# PixelGrid_Controller.net
KiCad netlist of a schematic drawn in EasyEDA Pro
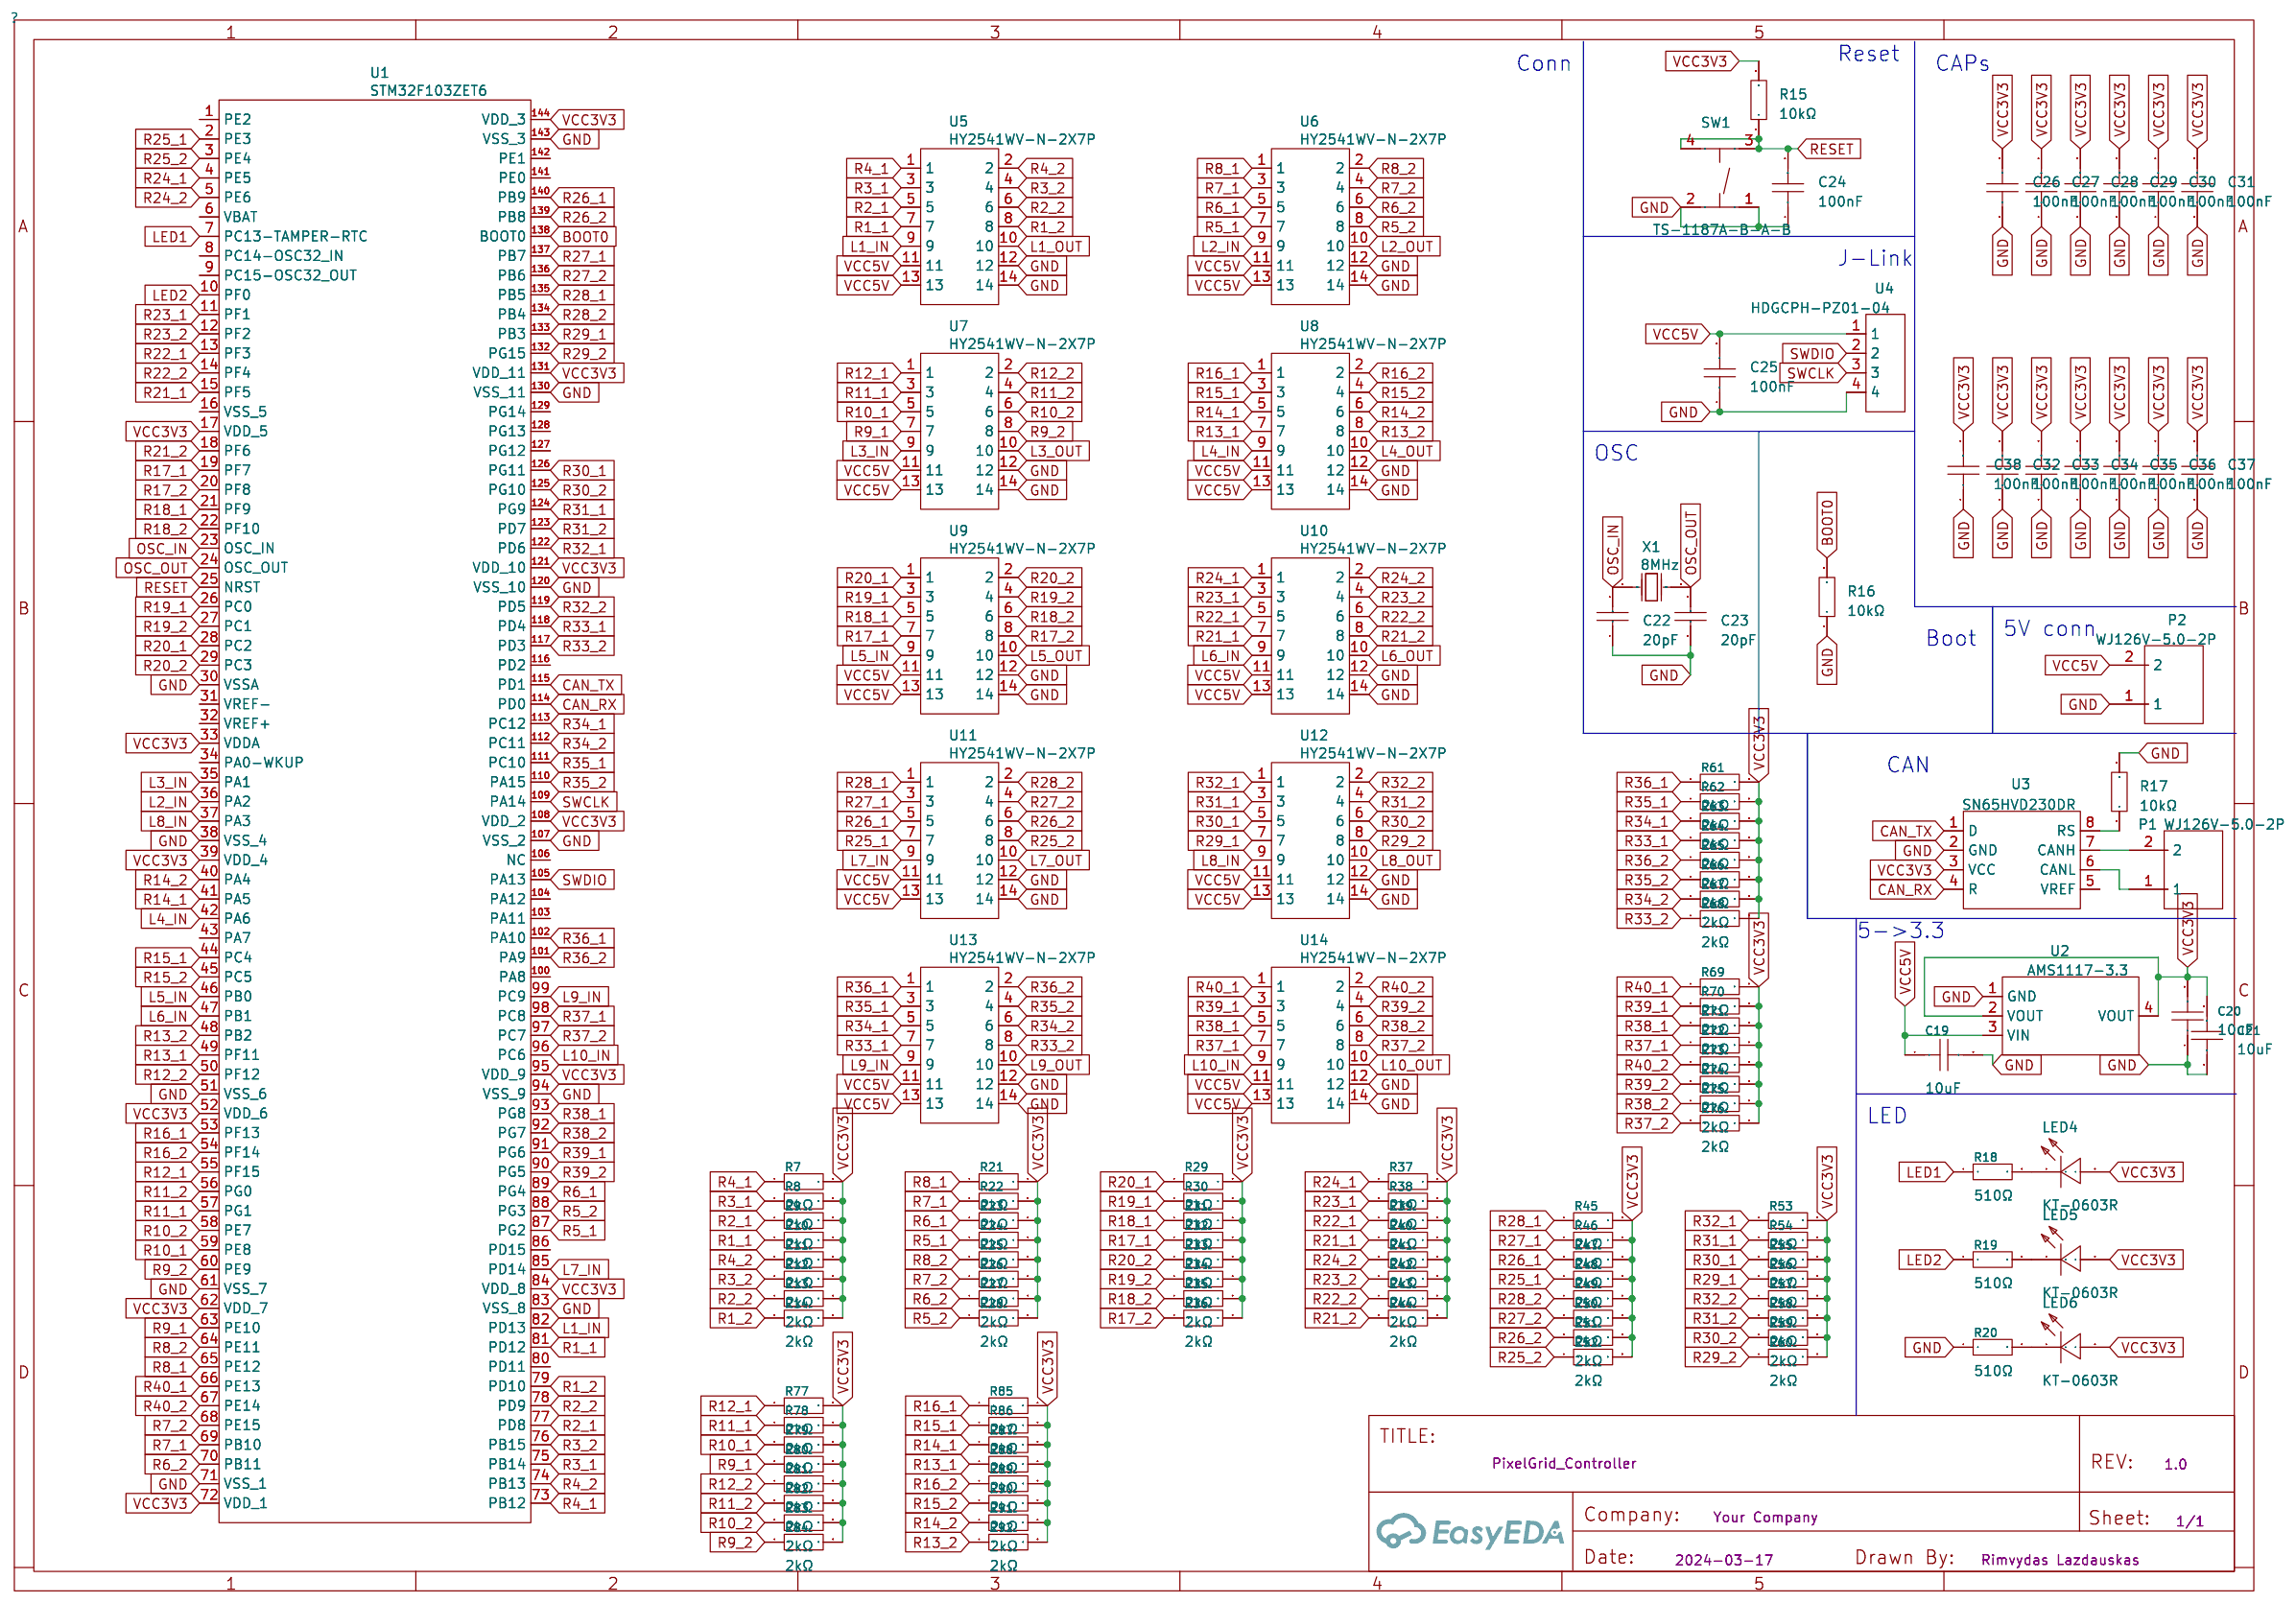
[diagram p0: schematic sheet]

(export (version "E")
  (design (tool "Eeschema 10.0.6"))
  (components
    (comp (ref "C19")
      (value "10uF")
      (footprint "easyedapro:C0603")
      (fields
        (field (name "Manufacturer Part") "CL10A106KP8NNNC")
        (field (name "Manufacturer") "SAMSUNG(三星)")
      )
      (libsource (lib "easyedapro") (part "CL10A106KP8NNNC"))
    )
    (comp (ref "C20")
      (value "10uF")
      (footprint "easyedapro:C0603")
      (fields
        (field (name "Manufacturer Part") "CL10A106KP8NNNC")
        (field (name "Manufacturer") "SAMSUNG(三星)")
      )
      (libsource (lib "easyedapro") (part "CL10A106KP8NNNC"))
    )
    (comp (ref "C21")
      (value "10uF")
      (footprint "easyedapro:C0603")
      (fields
        (field (name "Manufacturer Part") "CL10A106KP8NNNC")
        (field (name "Manufacturer") "SAMSUNG(三星)")
      )
      (libsource (lib "easyedapro") (part "CL10A106KP8NNNC"))
    )
    (comp (ref "C22")
      (value "20pF")
      (footprint "easyedapro:C0402")
      (fields (field (name "Manufacturer Part") "0402CG200J500NT") (field (name "Manufacturer") "FH(风华)"))
      (libsource (lib "easyedapro") (part "0402CG200J500NT"))
    )
    (comp (ref "C23")
      (value "20pF")
      (footprint "easyedapro:C0402")
      (fields (field (name "Manufacturer Part") "0402CG200J500NT") (field (name "Manufacturer") "FH(风华)"))
      (libsource (lib "easyedapro") (part "0402CG200J500NT"))
    )
    (comp (ref "C24")
      (value "100nF")
      (footprint "easyedapro:C0402")
      (fields
        (field (name "Manufacturer Part") "CL05B104KO5NNNC")
        (field (name "Manufacturer") "SAMSUNG(三星)")
      )
      (libsource (lib "easyedapro") (part "CL05B104KO5NNNC"))
    )
    (comp (ref "C25")
      (value "100nF")
      (footprint "easyedapro:C0402")
      (fields
        (field (name "Manufacturer Part") "CL05B104KO5NNNC")
        (field (name "Manufacturer") "SAMSUNG(三星)")
      )
      (libsource (lib "easyedapro") (part "CL05B104KO5NNNC"))
    )
    (comp (ref "C26")
      (value "100nF")
      (footprint "easyedapro:C0402")
      (fields
        (field (name "Manufacturer Part") "CL05B104KO5NNNC")
        (field (name "Manufacturer") "SAMSUNG(三星)")
      )
      (libsource (lib "easyedapro") (part "CL05B104KO5NNNC"))
    )
    (comp (ref "C27")
      (value "100nF")
      (footprint "easyedapro:C0402")
      (fields
        (field (name "Manufacturer Part") "CL05B104KO5NNNC")
        (field (name "Manufacturer") "SAMSUNG(三星)")
      )
      (libsource (lib "easyedapro") (part "CL05B104KO5NNNC"))
    )
    (comp (ref "C28")
      (value "100nF")
      (footprint "easyedapro:C0402")
      (fields
        (field (name "Manufacturer Part") "CL05B104KO5NNNC")
        (field (name "Manufacturer") "SAMSUNG(三星)")
      )
      (libsource (lib "easyedapro") (part "CL05B104KO5NNNC"))
    )
    (comp (ref "C29")
      (value "100nF")
      (footprint "easyedapro:C0402")
      (fields
        (field (name "Manufacturer Part") "CL05B104KO5NNNC")
        (field (name "Manufacturer") "SAMSUNG(三星)")
      )
      (libsource (lib "easyedapro") (part "CL05B104KO5NNNC"))
    )
    (comp (ref "C30")
      (value "100nF")
      (footprint "easyedapro:C0402")
      (fields
        (field (name "Manufacturer Part") "CL05B104KO5NNNC")
        (field (name "Manufacturer") "SAMSUNG(三星)")
      )
      (libsource (lib "easyedapro") (part "CL05B104KO5NNNC"))
    )
    (comp (ref "C31")
      (value "100nF")
      (footprint "easyedapro:C0402")
      (fields
        (field (name "Manufacturer Part") "CL05B104KO5NNNC")
        (field (name "Manufacturer") "SAMSUNG(三星)")
      )
      (libsource (lib "easyedapro") (part "CL05B104KO5NNNC"))
    )
    (comp (ref "C32")
      (value "100nF")
      (footprint "easyedapro:C0402")
      (fields
        (field (name "Manufacturer Part") "CL05B104KO5NNNC")
        (field (name "Manufacturer") "SAMSUNG(三星)")
      )
      (libsource (lib "easyedapro") (part "CL05B104KO5NNNC"))
    )
    (comp (ref "C33")
      (value "100nF")
      (footprint "easyedapro:C0402")
      (fields
        (field (name "Manufacturer Part") "CL05B104KO5NNNC")
        (field (name "Manufacturer") "SAMSUNG(三星)")
      )
      (libsource (lib "easyedapro") (part "CL05B104KO5NNNC"))
    )
    (comp (ref "C34")
      (value "100nF")
      (footprint "easyedapro:C0402")
      (fields
        (field (name "Manufacturer Part") "CL05B104KO5NNNC")
        (field (name "Manufacturer") "SAMSUNG(三星)")
      )
      (libsource (lib "easyedapro") (part "CL05B104KO5NNNC"))
    )
    (comp (ref "C35")
      (value "100nF")
      (footprint "easyedapro:C0402")
      (fields
        (field (name "Manufacturer Part") "CL05B104KO5NNNC")
        (field (name "Manufacturer") "SAMSUNG(三星)")
      )
      (libsource (lib "easyedapro") (part "CL05B104KO5NNNC"))
    )
    (comp (ref "C36")
      (value "100nF")
      (footprint "easyedapro:C0402")
      (fields
        (field (name "Manufacturer Part") "CL05B104KO5NNNC")
        (field (name "Manufacturer") "SAMSUNG(三星)")
      )
      (libsource (lib "easyedapro") (part "CL05B104KO5NNNC"))
    )
    (comp (ref "C37")
      (value "100nF")
      (footprint "easyedapro:C0402")
      (fields
        (field (name "Manufacturer Part") "CL05B104KO5NNNC")
        (field (name "Manufacturer") "SAMSUNG(三星)")
      )
      (libsource (lib "easyedapro") (part "CL05B104KO5NNNC"))
    )
    (comp (ref "C38")
      (value "100nF")
      (footprint "easyedapro:C0402")
      (fields
        (field (name "Manufacturer Part") "CL05B104KO5NNNC")
        (field (name "Manufacturer") "SAMSUNG(三星)")
      )
      (libsource (lib "easyedapro") (part "CL05B104KO5NNNC"))
    )
    (comp (ref "LED4")
      (value "KT-0603R")
      (footprint "easyedapro:LED0603-RD")
      (fields (field (name "Manufacturer") "KENTO"))
      (libsource (lib "easyedapro") (part "KT-0603R"))
    )
    (comp (ref "LED5")
      (value "KT-0603R")
      (footprint "easyedapro:LED0603-RD")
      (fields (field (name "Manufacturer") "KENTO"))
      (libsource (lib "easyedapro") (part "KT-0603R"))
    )
    (comp (ref "LED6")
      (value "KT-0603R")
      (footprint "easyedapro:LED0603-RD")
      (fields (field (name "Manufacturer") "KENTO"))
      (libsource (lib "easyedapro") (part "KT-0603R"))
    )
    (comp (ref "P1")
      (value "WJ126V-5.0-2P")
      (fields (field (name "Manufacturer") "KANGNEX(康奈克斯电气)"))
      (libsource (lib "easyedapro") (part "WJ126V-5.0-2P"))
    )
    (comp (ref "P2")
      (value "WJ126V-5.0-2P")
      (fields (field (name "Manufacturer") "KANGNEX(康奈克斯电气)"))
      (libsource (lib "easyedapro") (part "WJ126V-5.0-2P"))
    )
    (comp (ref "R7")
      (value "2kΩ")
      (footprint "easyedapro:R0402")
      (fields
        (field (name "Manufacturer Part") "0402WGF2001TCE")
        (field (name "Manufacturer") "UNI-ROYAL(厚声)")
      )
      (libsource (lib "easyedapro") (part "0402WGF2001TCE"))
    )
    (comp (ref "R8")
      (value "2kΩ")
      (footprint "easyedapro:R0402")
      (fields
        (field (name "Manufacturer Part") "0402WGF2001TCE")
        (field (name "Manufacturer") "UNI-ROYAL(厚声)")
      )
      (libsource (lib "easyedapro") (part "0402WGF2001TCE"))
    )
    (comp (ref "R9")
      (value "2kΩ")
      (footprint "easyedapro:R0402")
      (fields
        (field (name "Manufacturer Part") "0402WGF2001TCE")
        (field (name "Manufacturer") "UNI-ROYAL(厚声)")
      )
      (libsource (lib "easyedapro") (part "0402WGF2001TCE"))
    )
    (comp (ref "R10")
      (value "2kΩ")
      (footprint "easyedapro:R0402")
      (fields
        (field (name "Manufacturer Part") "0402WGF2001TCE")
        (field (name "Manufacturer") "UNI-ROYAL(厚声)")
      )
      (libsource (lib "easyedapro") (part "0402WGF2001TCE"))
    )
    (comp (ref "R11")
      (value "2kΩ")
      (footprint "easyedapro:R0402")
      (fields
        (field (name "Manufacturer Part") "0402WGF2001TCE")
        (field (name "Manufacturer") "UNI-ROYAL(厚声)")
      )
      (libsource (lib "easyedapro") (part "0402WGF2001TCE"))
    )
    (comp (ref "R12")
      (value "2kΩ")
      (footprint "easyedapro:R0402")
      (fields
        (field (name "Manufacturer Part") "0402WGF2001TCE")
        (field (name "Manufacturer") "UNI-ROYAL(厚声)")
      )
      (libsource (lib "easyedapro") (part "0402WGF2001TCE"))
    )
    (comp (ref "R13")
      (value "2kΩ")
      (footprint "easyedapro:R0402")
      (fields
        (field (name "Manufacturer Part") "0402WGF2001TCE")
        (field (name "Manufacturer") "UNI-ROYAL(厚声)")
      )
      (libsource (lib "easyedapro") (part "0402WGF2001TCE"))
    )
    (comp (ref "R14")
      (value "2kΩ")
      (footprint "easyedapro:R0402")
      (fields
        (field (name "Manufacturer Part") "0402WGF2001TCE")
        (field (name "Manufacturer") "UNI-ROYAL(厚声)")
      )
      (libsource (lib "easyedapro") (part "0402WGF2001TCE"))
    )
    (comp (ref "R15")
      (value "10kΩ")
      (footprint "easyedapro:R0402")
      (fields
        (field (name "Manufacturer Part") "0402WGF1002TCE")
        (field (name "Manufacturer") "UNI-ROYAL(厚声)")
      )
      (libsource (lib "easyedapro") (part "0402WGF1002TCE"))
    )
    (comp (ref "R16")
      (value "10kΩ")
      (footprint "easyedapro:R0402")
      (fields
        (field (name "Manufacturer Part") "0402WGF1002TCE")
        (field (name "Manufacturer") "UNI-ROYAL(厚声)")
      )
      (libsource (lib "easyedapro") (part "0402WGF1002TCE"))
    )
    (comp (ref "R17")
      (value "10kΩ")
      (footprint "easyedapro:R0402")
      (fields
        (field (name "Manufacturer Part") "0402WGF1002TCE")
        (field (name "Manufacturer") "UNI-ROYAL(厚声)")
      )
      (libsource (lib "easyedapro") (part "0402WGF1002TCE"))
    )
    (comp (ref "R18")
      (value "510Ω")
      (footprint "easyedapro:R0402")
      (fields
        (field (name "Manufacturer Part") "0402WGF5100TCE")
        (field (name "Manufacturer") "UNI-ROYAL(厚声)")
      )
      (libsource (lib "easyedapro") (part "0402WGF5100TCE"))
    )
    (comp (ref "R19")
      (value "510Ω")
      (footprint "easyedapro:R0402")
      (fields
        (field (name "Manufacturer Part") "0402WGF5100TCE")
        (field (name "Manufacturer") "UNI-ROYAL(厚声)")
      )
      (libsource (lib "easyedapro") (part "0402WGF5100TCE"))
    )
    (comp (ref "R20")
      (value "510Ω")
      (footprint "easyedapro:R0402")
      (fields
        (field (name "Manufacturer Part") "0402WGF5100TCE")
        (field (name "Manufacturer") "UNI-ROYAL(厚声)")
      )
      (libsource (lib "easyedapro") (part "0402WGF5100TCE"))
    )
    (comp (ref "R21")
      (value "2kΩ")
      (footprint "easyedapro:R0402")
      (fields
        (field (name "Manufacturer Part") "0402WGF2001TCE")
        (field (name "Manufacturer") "UNI-ROYAL(厚声)")
      )
      (libsource (lib "easyedapro") (part "0402WGF2001TCE"))
    )
    (comp (ref "R22")
      (value "2kΩ")
      (footprint "easyedapro:R0402")
      (fields
        (field (name "Manufacturer Part") "0402WGF2001TCE")
        (field (name "Manufacturer") "UNI-ROYAL(厚声)")
      )
      (libsource (lib "easyedapro") (part "0402WGF2001TCE"))
    )
    (comp (ref "R23")
      (value "2kΩ")
      (footprint "easyedapro:R0402")
      (fields
        (field (name "Manufacturer Part") "0402WGF2001TCE")
        (field (name "Manufacturer") "UNI-ROYAL(厚声)")
      )
      (libsource (lib "easyedapro") (part "0402WGF2001TCE"))
    )
    (comp (ref "R24")
      (value "2kΩ")
      (footprint "easyedapro:R0402")
      (fields
        (field (name "Manufacturer Part") "0402WGF2001TCE")
        (field (name "Manufacturer") "UNI-ROYAL(厚声)")
      )
      (libsource (lib "easyedapro") (part "0402WGF2001TCE"))
    )
    (comp (ref "R25")
      (value "2kΩ")
      (footprint "easyedapro:R0402")
      (fields
        (field (name "Manufacturer Part") "0402WGF2001TCE")
        (field (name "Manufacturer") "UNI-ROYAL(厚声)")
      )
      (libsource (lib "easyedapro") (part "0402WGF2001TCE"))
    )
    (comp (ref "R26")
      (value "2kΩ")
      (footprint "easyedapro:R0402")
      (fields
        (field (name "Manufacturer Part") "0402WGF2001TCE")
        (field (name "Manufacturer") "UNI-ROYAL(厚声)")
      )
      (libsource (lib "easyedapro") (part "0402WGF2001TCE"))
    )
    (comp (ref "R27")
      (value "2kΩ")
      (footprint "easyedapro:R0402")
      (fields
        (field (name "Manufacturer Part") "0402WGF2001TCE")
        (field (name "Manufacturer") "UNI-ROYAL(厚声)")
      )
      (libsource (lib "easyedapro") (part "0402WGF2001TCE"))
    )
    (comp (ref "R28")
      (value "2kΩ")
      (footprint "easyedapro:R0402")
      (fields
        (field (name "Manufacturer Part") "0402WGF2001TCE")
        (field (name "Manufacturer") "UNI-ROYAL(厚声)")
      )
      (libsource (lib "easyedapro") (part "0402WGF2001TCE"))
    )
    (comp (ref "R29")
      (value "2kΩ")
      (footprint "easyedapro:R0402")
      (fields
        (field (name "Manufacturer Part") "0402WGF2001TCE")
        (field (name "Manufacturer") "UNI-ROYAL(厚声)")
      )
      (libsource (lib "easyedapro") (part "0402WGF2001TCE"))
    )
    (comp (ref "R30")
      (value "2kΩ")
      (footprint "easyedapro:R0402")
      (fields
        (field (name "Manufacturer Part") "0402WGF2001TCE")
        (field (name "Manufacturer") "UNI-ROYAL(厚声)")
      )
      (libsource (lib "easyedapro") (part "0402WGF2001TCE"))
    )
    (comp (ref "R31")
      (value "2kΩ")
      (footprint "easyedapro:R0402")
      (fields
        (field (name "Manufacturer Part") "0402WGF2001TCE")
        (field (name "Manufacturer") "UNI-ROYAL(厚声)")
      )
      (libsource (lib "easyedapro") (part "0402WGF2001TCE"))
    )
    (comp (ref "R32")
      (value "2kΩ")
      (footprint "easyedapro:R0402")
      (fields
        (field (name "Manufacturer Part") "0402WGF2001TCE")
        (field (name "Manufacturer") "UNI-ROYAL(厚声)")
      )
      (libsource (lib "easyedapro") (part "0402WGF2001TCE"))
    )
    (comp (ref "R33")
      (value "2kΩ")
      (footprint "easyedapro:R0402")
      (fields
        (field (name "Manufacturer Part") "0402WGF2001TCE")
        (field (name "Manufacturer") "UNI-ROYAL(厚声)")
      )
      (libsource (lib "easyedapro") (part "0402WGF2001TCE"))
    )
    (comp (ref "R34")
      (value "2kΩ")
      (footprint "easyedapro:R0402")
      (fields
        (field (name "Manufacturer Part") "0402WGF2001TCE")
        (field (name "Manufacturer") "UNI-ROYAL(厚声)")
      )
      (libsource (lib "easyedapro") (part "0402WGF2001TCE"))
    )
    (comp (ref "R35")
      (value "2kΩ")
      (footprint "easyedapro:R0402")
      (fields
        (field (name "Manufacturer Part") "0402WGF2001TCE")
        (field (name "Manufacturer") "UNI-ROYAL(厚声)")
      )
      (libsource (lib "easyedapro") (part "0402WGF2001TCE"))
    )
    (comp (ref "R36")
      (value "2kΩ")
      (footprint "easyedapro:R0402")
      (fields
        (field (name "Manufacturer Part") "0402WGF2001TCE")
        (field (name "Manufacturer") "UNI-ROYAL(厚声)")
      )
      (libsource (lib "easyedapro") (part "0402WGF2001TCE"))
    )
    (comp (ref "R37")
      (value "2kΩ")
      (footprint "easyedapro:R0402")
      (fields
        (field (name "Manufacturer Part") "0402WGF2001TCE")
        (field (name "Manufacturer") "UNI-ROYAL(厚声)")
      )
      (libsource (lib "easyedapro") (part "0402WGF2001TCE"))
    )
    (comp (ref "R38")
      (value "2kΩ")
      (footprint "easyedapro:R0402")
      (fields
        (field (name "Manufacturer Part") "0402WGF2001TCE")
        (field (name "Manufacturer") "UNI-ROYAL(厚声)")
      )
      (libsource (lib "easyedapro") (part "0402WGF2001TCE"))
    )
    (comp (ref "R39")
      (value "2kΩ")
      (footprint "easyedapro:R0402")
      (fields
        (field (name "Manufacturer Part") "0402WGF2001TCE")
        (field (name "Manufacturer") "UNI-ROYAL(厚声)")
      )
      (libsource (lib "easyedapro") (part "0402WGF2001TCE"))
    )
    (comp (ref "R40")
      (value "2kΩ")
      (footprint "easyedapro:R0402")
      (fields
        (field (name "Manufacturer Part") "0402WGF2001TCE")
        (field (name "Manufacturer") "UNI-ROYAL(厚声)")
      )
      (libsource (lib "easyedapro") (part "0402WGF2001TCE"))
    )
    (comp (ref "R41")
      (value "2kΩ")
      (footprint "easyedapro:R0402")
      (fields
        (field (name "Manufacturer Part") "0402WGF2001TCE")
        (field (name "Manufacturer") "UNI-ROYAL(厚声)")
      )
      (libsource (lib "easyedapro") (part "0402WGF2001TCE"))
    )
    (comp (ref "R42")
      (value "2kΩ")
      (footprint "easyedapro:R0402")
      (fields
        (field (name "Manufacturer Part") "0402WGF2001TCE")
        (field (name "Manufacturer") "UNI-ROYAL(厚声)")
      )
      (libsource (lib "easyedapro") (part "0402WGF2001TCE"))
    )
    (comp (ref "R43")
      (value "2kΩ")
      (footprint "easyedapro:R0402")
      (fields
        (field (name "Manufacturer Part") "0402WGF2001TCE")
        (field (name "Manufacturer") "UNI-ROYAL(厚声)")
      )
      (libsource (lib "easyedapro") (part "0402WGF2001TCE"))
    )
    (comp (ref "R44")
      (value "2kΩ")
      (footprint "easyedapro:R0402")
      (fields
        (field (name "Manufacturer Part") "0402WGF2001TCE")
        (field (name "Manufacturer") "UNI-ROYAL(厚声)")
      )
      (libsource (lib "easyedapro") (part "0402WGF2001TCE"))
    )
    (comp (ref "R45")
      (value "2kΩ")
      (footprint "easyedapro:R0402")
      (fields
        (field (name "Manufacturer Part") "0402WGF2001TCE")
        (field (name "Manufacturer") "UNI-ROYAL(厚声)")
      )
      (libsource (lib "easyedapro") (part "0402WGF2001TCE"))
    )
    (comp (ref "R46")
      (value "2kΩ")
      (footprint "easyedapro:R0402")
      (fields
        (field (name "Manufacturer Part") "0402WGF2001TCE")
        (field (name "Manufacturer") "UNI-ROYAL(厚声)")
      )
      (libsource (lib "easyedapro") (part "0402WGF2001TCE"))
    )
    (comp (ref "R47")
      (value "2kΩ")
      (footprint "easyedapro:R0402")
      (fields
        (field (name "Manufacturer Part") "0402WGF2001TCE")
        (field (name "Manufacturer") "UNI-ROYAL(厚声)")
      )
      (libsource (lib "easyedapro") (part "0402WGF2001TCE"))
    )
    (comp (ref "R48")
      (value "2kΩ")
      (footprint "easyedapro:R0402")
      (fields
        (field (name "Manufacturer Part") "0402WGF2001TCE")
        (field (name "Manufacturer") "UNI-ROYAL(厚声)")
      )
      (libsource (lib "easyedapro") (part "0402WGF2001TCE"))
    )
    (comp (ref "R49")
      (value "2kΩ")
      (footprint "easyedapro:R0402")
      (fields
        (field (name "Manufacturer Part") "0402WGF2001TCE")
        (field (name "Manufacturer") "UNI-ROYAL(厚声)")
      )
      (libsource (lib "easyedapro") (part "0402WGF2001TCE"))
    )
    (comp (ref "R50")
      (value "2kΩ")
      (footprint "easyedapro:R0402")
      (fields
        (field (name "Manufacturer Part") "0402WGF2001TCE")
        (field (name "Manufacturer") "UNI-ROYAL(厚声)")
      )
      (libsource (lib "easyedapro") (part "0402WGF2001TCE"))
    )
    (comp (ref "R51")
      (value "2kΩ")
      (footprint "easyedapro:R0402")
      (fields
        (field (name "Manufacturer Part") "0402WGF2001TCE")
        (field (name "Manufacturer") "UNI-ROYAL(厚声)")
      )
      (libsource (lib "easyedapro") (part "0402WGF2001TCE"))
    )
    (comp (ref "R52")
      (value "2kΩ")
      (footprint "easyedapro:R0402")
      (fields
        (field (name "Manufacturer Part") "0402WGF2001TCE")
        (field (name "Manufacturer") "UNI-ROYAL(厚声)")
      )
      (libsource (lib "easyedapro") (part "0402WGF2001TCE"))
    )
    (comp (ref "R53")
      (value "2kΩ")
      (footprint "easyedapro:R0402")
      (fields
        (field (name "Manufacturer Part") "0402WGF2001TCE")
        (field (name "Manufacturer") "UNI-ROYAL(厚声)")
      )
      (libsource (lib "easyedapro") (part "0402WGF2001TCE"))
    )
    (comp (ref "R54")
      (value "2kΩ")
      (footprint "easyedapro:R0402")
      (fields
        (field (name "Manufacturer Part") "0402WGF2001TCE")
        (field (name "Manufacturer") "UNI-ROYAL(厚声)")
      )
      (libsource (lib "easyedapro") (part "0402WGF2001TCE"))
    )
    (comp (ref "R55")
      (value "2kΩ")
      (footprint "easyedapro:R0402")
      (fields
        (field (name "Manufacturer Part") "0402WGF2001TCE")
        (field (name "Manufacturer") "UNI-ROYAL(厚声)")
      )
      (libsource (lib "easyedapro") (part "0402WGF2001TCE"))
    )
    (comp (ref "R56")
      (value "2kΩ")
      (footprint "easyedapro:R0402")
      (fields
        (field (name "Manufacturer Part") "0402WGF2001TCE")
        (field (name "Manufacturer") "UNI-ROYAL(厚声)")
      )
      (libsource (lib "easyedapro") (part "0402WGF2001TCE"))
    )
    (comp (ref "R57")
      (value "2kΩ")
      (footprint "easyedapro:R0402")
      (fields
        (field (name "Manufacturer Part") "0402WGF2001TCE")
        (field (name "Manufacturer") "UNI-ROYAL(厚声)")
      )
      (libsource (lib "easyedapro") (part "0402WGF2001TCE"))
    )
    (comp (ref "R58")
      (value "2kΩ")
      (footprint "easyedapro:R0402")
      (fields
        (field (name "Manufacturer Part") "0402WGF2001TCE")
        (field (name "Manufacturer") "UNI-ROYAL(厚声)")
      )
      (libsource (lib "easyedapro") (part "0402WGF2001TCE"))
    )
    (comp (ref "R59")
      (value "2kΩ")
      (footprint "easyedapro:R0402")
      (fields
        (field (name "Manufacturer Part") "0402WGF2001TCE")
        (field (name "Manufacturer") "UNI-ROYAL(厚声)")
      )
      (libsource (lib "easyedapro") (part "0402WGF2001TCE"))
    )
    (comp (ref "R60")
      (value "2kΩ")
      (footprint "easyedapro:R0402")
      (fields
        (field (name "Manufacturer Part") "0402WGF2001TCE")
        (field (name "Manufacturer") "UNI-ROYAL(厚声)")
      )
      (libsource (lib "easyedapro") (part "0402WGF2001TCE"))
    )
    (comp (ref "R61")
      (value "2kΩ")
      (footprint "easyedapro:R0402")
      (fields
        (field (name "Manufacturer Part") "0402WGF2001TCE")
        (field (name "Manufacturer") "UNI-ROYAL(厚声)")
      )
      (libsource (lib "easyedapro") (part "0402WGF2001TCE"))
    )
    (comp (ref "R62")
      (value "2kΩ")
      (footprint "easyedapro:R0402")
      (fields
        (field (name "Manufacturer Part") "0402WGF2001TCE")
        (field (name "Manufacturer") "UNI-ROYAL(厚声)")
      )
      (libsource (lib "easyedapro") (part "0402WGF2001TCE"))
    )
    (comp (ref "R63")
      (value "2kΩ")
      (footprint "easyedapro:R0402")
      (fields
        (field (name "Manufacturer Part") "0402WGF2001TCE")
        (field (name "Manufacturer") "UNI-ROYAL(厚声)")
      )
      (libsource (lib "easyedapro") (part "0402WGF2001TCE"))
    )
    (comp (ref "R64")
      (value "2kΩ")
      (footprint "easyedapro:R0402")
      (fields
        (field (name "Manufacturer Part") "0402WGF2001TCE")
        (field (name "Manufacturer") "UNI-ROYAL(厚声)")
      )
      (libsource (lib "easyedapro") (part "0402WGF2001TCE"))
    )
    (comp (ref "R65")
      (value "2kΩ")
      (footprint "easyedapro:R0402")
      (fields
        (field (name "Manufacturer Part") "0402WGF2001TCE")
        (field (name "Manufacturer") "UNI-ROYAL(厚声)")
      )
      (libsource (lib "easyedapro") (part "0402WGF2001TCE"))
    )
    (comp (ref "R66")
      (value "2kΩ")
      (footprint "easyedapro:R0402")
      (fields
        (field (name "Manufacturer Part") "0402WGF2001TCE")
        (field (name "Manufacturer") "UNI-ROYAL(厚声)")
      )
      (libsource (lib "easyedapro") (part "0402WGF2001TCE"))
    )
    (comp (ref "R67")
      (value "2kΩ")
      (footprint "easyedapro:R0402")
      (fields
        (field (name "Manufacturer Part") "0402WGF2001TCE")
        (field (name "Manufacturer") "UNI-ROYAL(厚声)")
      )
      (libsource (lib "easyedapro") (part "0402WGF2001TCE"))
    )
    (comp (ref "R68")
      (value "2kΩ")
      (footprint "easyedapro:R0402")
      (fields
        (field (name "Manufacturer Part") "0402WGF2001TCE")
        (field (name "Manufacturer") "UNI-ROYAL(厚声)")
      )
      (libsource (lib "easyedapro") (part "0402WGF2001TCE"))
    )
    (comp (ref "R69")
      (value "2kΩ")
      (footprint "easyedapro:R0402")
      (fields
        (field (name "Manufacturer Part") "0402WGF2001TCE")
        (field (name "Manufacturer") "UNI-ROYAL(厚声)")
      )
      (libsource (lib "easyedapro") (part "0402WGF2001TCE"))
    )
    (comp (ref "R70")
      (value "2kΩ")
      (footprint "easyedapro:R0402")
      (fields
        (field (name "Manufacturer Part") "0402WGF2001TCE")
        (field (name "Manufacturer") "UNI-ROYAL(厚声)")
      )
      (libsource (lib "easyedapro") (part "0402WGF2001TCE"))
    )
    (comp (ref "R71")
      (value "2kΩ")
      (footprint "easyedapro:R0402")
      (fields
        (field (name "Manufacturer Part") "0402WGF2001TCE")
        (field (name "Manufacturer") "UNI-ROYAL(厚声)")
      )
      (libsource (lib "easyedapro") (part "0402WGF2001TCE"))
    )
    (comp (ref "R72")
      (value "2kΩ")
      (footprint "easyedapro:R0402")
      (fields
        (field (name "Manufacturer Part") "0402WGF2001TCE")
        (field (name "Manufacturer") "UNI-ROYAL(厚声)")
      )
      (libsource (lib "easyedapro") (part "0402WGF2001TCE"))
    )
    (comp (ref "R73")
      (value "2kΩ")
      (footprint "easyedapro:R0402")
      (fields
        (field (name "Manufacturer Part") "0402WGF2001TCE")
        (field (name "Manufacturer") "UNI-ROYAL(厚声)")
      )
      (libsource (lib "easyedapro") (part "0402WGF2001TCE"))
    )
    (comp (ref "R74")
      (value "2kΩ")
      (footprint "easyedapro:R0402")
      (fields
        (field (name "Manufacturer Part") "0402WGF2001TCE")
        (field (name "Manufacturer") "UNI-ROYAL(厚声)")
      )
      (libsource (lib "easyedapro") (part "0402WGF2001TCE"))
    )
    (comp (ref "R75")
      (value "2kΩ")
      (footprint "easyedapro:R0402")
      (fields
        (field (name "Manufacturer Part") "0402WGF2001TCE")
        (field (name "Manufacturer") "UNI-ROYAL(厚声)")
      )
      (libsource (lib "easyedapro") (part "0402WGF2001TCE"))
    )
    (comp (ref "R76")
      (value "2kΩ")
      (footprint "easyedapro:R0402")
      (fields
        (field (name "Manufacturer Part") "0402WGF2001TCE")
        (field (name "Manufacturer") "UNI-ROYAL(厚声)")
      )
      (libsource (lib "easyedapro") (part "0402WGF2001TCE"))
    )
    (comp (ref "R77")
      (value "2kΩ")
      (footprint "easyedapro:R0402")
      (fields
        (field (name "Manufacturer Part") "0402WGF2001TCE")
        (field (name "Manufacturer") "UNI-ROYAL(厚声)")
      )
      (libsource (lib "easyedapro") (part "0402WGF2001TCE"))
    )
    (comp (ref "R78")
      (value "2kΩ")
      (footprint "easyedapro:R0402")
      (fields
        (field (name "Manufacturer Part") "0402WGF2001TCE")
        (field (name "Manufacturer") "UNI-ROYAL(厚声)")
      )
      (libsource (lib "easyedapro") (part "0402WGF2001TCE"))
    )
    (comp (ref "R79")
      (value "2kΩ")
      (footprint "easyedapro:R0402")
      (fields
        (field (name "Manufacturer Part") "0402WGF2001TCE")
        (field (name "Manufacturer") "UNI-ROYAL(厚声)")
      )
      (libsource (lib "easyedapro") (part "0402WGF2001TCE"))
    )
    (comp (ref "R80")
      (value "2kΩ")
      (footprint "easyedapro:R0402")
      (fields
        (field (name "Manufacturer Part") "0402WGF2001TCE")
        (field (name "Manufacturer") "UNI-ROYAL(厚声)")
      )
      (libsource (lib "easyedapro") (part "0402WGF2001TCE"))
    )
    (comp (ref "R81")
      (value "2kΩ")
      (footprint "easyedapro:R0402")
      (fields
        (field (name "Manufacturer Part") "0402WGF2001TCE")
        (field (name "Manufacturer") "UNI-ROYAL(厚声)")
      )
      (libsource (lib "easyedapro") (part "0402WGF2001TCE"))
    )
    (comp (ref "R82")
      (value "2kΩ")
      (footprint "easyedapro:R0402")
      (fields
        (field (name "Manufacturer Part") "0402WGF2001TCE")
        (field (name "Manufacturer") "UNI-ROYAL(厚声)")
      )
      (libsource (lib "easyedapro") (part "0402WGF2001TCE"))
    )
    (comp (ref "R83")
      (value "2kΩ")
      (footprint "easyedapro:R0402")
      (fields
        (field (name "Manufacturer Part") "0402WGF2001TCE")
        (field (name "Manufacturer") "UNI-ROYAL(厚声)")
      )
      (libsource (lib "easyedapro") (part "0402WGF2001TCE"))
    )
    (comp (ref "R84")
      (value "2kΩ")
      (footprint "easyedapro:R0402")
      (fields
        (field (name "Manufacturer Part") "0402WGF2001TCE")
        (field (name "Manufacturer") "UNI-ROYAL(厚声)")
      )
      (libsource (lib "easyedapro") (part "0402WGF2001TCE"))
    )
    (comp (ref "R85")
      (value "2kΩ")
      (footprint "easyedapro:R0402")
      (fields
        (field (name "Manufacturer Part") "0402WGF2001TCE")
        (field (name "Manufacturer") "UNI-ROYAL(厚声)")
      )
      (libsource (lib "easyedapro") (part "0402WGF2001TCE"))
    )
    (comp (ref "R86")
      (value "2kΩ")
      (footprint "easyedapro:R0402")
      (fields
        (field (name "Manufacturer Part") "0402WGF2001TCE")
        (field (name "Manufacturer") "UNI-ROYAL(厚声)")
      )
      (libsource (lib "easyedapro") (part "0402WGF2001TCE"))
    )
    (comp (ref "R87")
      (value "2kΩ")
      (footprint "easyedapro:R0402")
      (fields
        (field (name "Manufacturer Part") "0402WGF2001TCE")
        (field (name "Manufacturer") "UNI-ROYAL(厚声)")
      )
      (libsource (lib "easyedapro") (part "0402WGF2001TCE"))
    )
    (comp (ref "R88")
      (value "2kΩ")
      (footprint "easyedapro:R0402")
      (fields
        (field (name "Manufacturer Part") "0402WGF2001TCE")
        (field (name "Manufacturer") "UNI-ROYAL(厚声)")
      )
      (libsource (lib "easyedapro") (part "0402WGF2001TCE"))
    )
    (comp (ref "R89")
      (value "2kΩ")
      (footprint "easyedapro:R0402")
      (fields
        (field (name "Manufacturer Part") "0402WGF2001TCE")
        (field (name "Manufacturer") "UNI-ROYAL(厚声)")
      )
      (libsource (lib "easyedapro") (part "0402WGF2001TCE"))
    )
    (comp (ref "R90")
      (value "2kΩ")
      (footprint "easyedapro:R0402")
      (fields
        (field (name "Manufacturer Part") "0402WGF2001TCE")
        (field (name "Manufacturer") "UNI-ROYAL(厚声)")
      )
      (libsource (lib "easyedapro") (part "0402WGF2001TCE"))
    )
    (comp (ref "R91")
      (value "2kΩ")
      (footprint "easyedapro:R0402")
      (fields
        (field (name "Manufacturer Part") "0402WGF2001TCE")
        (field (name "Manufacturer") "UNI-ROYAL(厚声)")
      )
      (libsource (lib "easyedapro") (part "0402WGF2001TCE"))
    )
    (comp (ref "R92")
      (value "2kΩ")
      (footprint "easyedapro:R0402")
      (fields
        (field (name "Manufacturer Part") "0402WGF2001TCE")
        (field (name "Manufacturer") "UNI-ROYAL(厚声)")
      )
      (libsource (lib "easyedapro") (part "0402WGF2001TCE"))
    )
    (comp (ref "SW1")
      (value "TS-1187A-B-A-B")
      (fields (field (name "Manufacturer") "XKB Connectivity(中国星坤)"))
      (libsource (lib "easyedapro") (part "TS-1187A-B-A-B"))
    )
    (comp (ref "U1")
      (value "STM32F103ZET6")
      (fields (field (name "Manufacturer") "ST(意法半导体)"))
      (libsource (lib "easyedapro") (part "STM32F103ZET6"))
    )
    (comp (ref "U2")
      (value "AMS1117-3.3")
      (fields (field (name "Manufacturer") "AMS"))
      (libsource (lib "easyedapro") (part "AMS1117-3.3"))
    )
    (comp (ref "U3")
      (value "SN65HVD230DR")
      (fields (field (name "Manufacturer") "TI(德州仪器)"))
      (libsource (lib "easyedapro") (part "SN65HVD230DR"))
    )
    (comp (ref "U4")
      (value "HDGCPH-PZ01-04")
      (fields (field (name "Manufacturer") "HDGC(华德共创)"))
      (libsource (lib "easyedapro") (part "HDGCPH-PZ01-04"))
    )
    (comp (ref "U5")
      (value "HY2541WV-N-2X7P")
      (fields
        (field (name "Manufacturer Part") "HY2541WV-N-2x7P")
        (field (name "Manufacturer") "HanElectricity(瀚源)")
      )
      (libsource (lib "easyedapro") (part "HY2541WV-N-2X7P"))
    )
    (comp (ref "U6")
      (value "HY2541WV-N-2X7P")
      (fields
        (field (name "Manufacturer Part") "HY2541WV-N-2x7P")
        (field (name "Manufacturer") "HanElectricity(瀚源)")
      )
      (libsource (lib "easyedapro") (part "HY2541WV-N-2X7P"))
    )
    (comp (ref "U7")
      (value "HY2541WV-N-2X7P")
      (fields
        (field (name "Manufacturer Part") "HY2541WV-N-2x7P")
        (field (name "Manufacturer") "HanElectricity(瀚源)")
      )
      (libsource (lib "easyedapro") (part "HY2541WV-N-2X7P"))
    )
    (comp (ref "U8")
      (value "HY2541WV-N-2X7P")
      (fields
        (field (name "Manufacturer Part") "HY2541WV-N-2x7P")
        (field (name "Manufacturer") "HanElectricity(瀚源)")
      )
      (libsource (lib "easyedapro") (part "HY2541WV-N-2X7P"))
    )
    (comp (ref "U9")
      (value "HY2541WV-N-2X7P")
      (fields
        (field (name "Manufacturer Part") "HY2541WV-N-2x7P")
        (field (name "Manufacturer") "HanElectricity(瀚源)")
      )
      (libsource (lib "easyedapro") (part "HY2541WV-N-2X7P"))
    )
    (comp (ref "U10")
      (value "HY2541WV-N-2X7P")
      (fields
        (field (name "Manufacturer Part") "HY2541WV-N-2x7P")
        (field (name "Manufacturer") "HanElectricity(瀚源)")
      )
      (libsource (lib "easyedapro") (part "HY2541WV-N-2X7P"))
    )
    (comp (ref "U11")
      (value "HY2541WV-N-2X7P")
      (fields
        (field (name "Manufacturer Part") "HY2541WV-N-2x7P")
        (field (name "Manufacturer") "HanElectricity(瀚源)")
      )
      (libsource (lib "easyedapro") (part "HY2541WV-N-2X7P"))
    )
    (comp (ref "U12")
      (value "HY2541WV-N-2X7P")
      (fields
        (field (name "Manufacturer Part") "HY2541WV-N-2x7P")
        (field (name "Manufacturer") "HanElectricity(瀚源)")
      )
      (libsource (lib "easyedapro") (part "HY2541WV-N-2X7P"))
    )
    (comp (ref "U13")
      (value "HY2541WV-N-2X7P")
      (fields
        (field (name "Manufacturer Part") "HY2541WV-N-2x7P")
        (field (name "Manufacturer") "HanElectricity(瀚源)")
      )
      (libsource (lib "easyedapro") (part "HY2541WV-N-2X7P"))
    )
    (comp (ref "U14")
      (value "HY2541WV-N-2X7P")
      (fields
        (field (name "Manufacturer Part") "HY2541WV-N-2x7P")
        (field (name "Manufacturer") "HanElectricity(瀚源)")
      )
      (libsource (lib "easyedapro") (part "HY2541WV-N-2X7P"))
    )
    (comp (ref "X1")
      (value "8MHz")
      (fields (field (name "Manufacturer Part") "X50328MSB2GI") (field (name "Manufacturer") "YXC(扬兴晶振)"))
      (libsource (lib "easyedapro") (part "8MHz"))
    )
  )
  (nets
    (net (code "1") (name "BOOT0") (class "Default")
      (node (ref "R16") (pin "2") (pinfunction "2_2") (pintype "input"))
      (node (ref "U1") (pin "138") (pinfunction "BOOT0_138") (pintype "unspecified"))
    )
    (net (code "2") (name "CAN_RX") (class "Default")
      (node (ref "U1") (pin "114") (pinfunction "PD0_114") (pintype "unspecified"))
      (node (ref "U3") (pin "4") (pinfunction "R_4") (pintype "unspecified"))
    )
    (net (code "3") (name "CAN_TX") (class "Default")
      (node (ref "U1") (pin "115") (pinfunction "PD1_115") (pintype "unspecified"))
      (node (ref "U3") (pin "1") (pinfunction "D_1") (pintype "unspecified"))
    )
    (net (code "4") (name "GND") (class "Default")
      (node (ref "C19") (pin "2") (pinfunction "2_2") (pintype "input"))
      (node (ref "C20") (pin "1") (pinfunction "1_1") (pintype "input"))
      (node (ref "C21") (pin "1") (pinfunction "1_1") (pintype "input"))
      (node (ref "C22") (pin "1") (pinfunction "1_1") (pintype "input"))
      (node (ref "C23") (pin "1") (pinfunction "1_1") (pintype "input"))
      (node (ref "C24") (pin "1") (pinfunction "1_1") (pintype "unspecified"))
      (node (ref "C25") (pin "1") (pinfunction "1_1") (pintype "unspecified"))
      (node (ref "C26") (pin "1") (pinfunction "1_1") (pintype "unspecified"))
      (node (ref "C27") (pin "1") (pinfunction "1_1") (pintype "unspecified"))
      (node (ref "C28") (pin "1") (pinfunction "1_1") (pintype "unspecified"))
      (node (ref "C29") (pin "1") (pinfunction "1_1") (pintype "unspecified"))
      (node (ref "C30") (pin "1") (pinfunction "1_1") (pintype "unspecified"))
      (node (ref "C31") (pin "1") (pinfunction "1_1") (pintype "unspecified"))
      (node (ref "C32") (pin "1") (pinfunction "1_1") (pintype "unspecified"))
      (node (ref "C33") (pin "1") (pinfunction "1_1") (pintype "unspecified"))
      (node (ref "C34") (pin "1") (pinfunction "1_1") (pintype "unspecified"))
      (node (ref "C35") (pin "1") (pinfunction "1_1") (pintype "unspecified"))
      (node (ref "C36") (pin "1") (pinfunction "1_1") (pintype "unspecified"))
      (node (ref "C37") (pin "1") (pinfunction "1_1") (pintype "unspecified"))
      (node (ref "C38") (pin "1") (pinfunction "1_1") (pintype "unspecified"))
      (node (ref "P2") (pin "1") (pinfunction "1_1") (pintype "input"))
      (node (ref "R16") (pin "1") (pinfunction "1_1") (pintype "input"))
      (node (ref "R17") (pin "2") (pinfunction "2_2") (pintype "input"))
      (node (ref "R20") (pin "1") (pinfunction "1_1") (pintype "input"))
      (node (ref "SW1") (pin "1") (pinfunction "A_1") (pintype "unspecified"))
      (node (ref "SW1") (pin "2") (pinfunction "B_2") (pintype "unspecified"))
      (node (ref "U1") (pin "107") (pinfunction "VSS_2_107") (pintype "unspecified"))
      (node (ref "U1") (pin "120") (pinfunction "VSS_10_120") (pintype "unspecified"))
      (node (ref "U1") (pin "130") (pinfunction "VSS_11_130") (pintype "unspecified"))
      (node (ref "U1") (pin "143") (pinfunction "VSS_3_143") (pintype "unspecified"))
      (node (ref "U1") (pin "30") (pinfunction "VSSA_30") (pintype "unspecified"))
      (node (ref "U1") (pin "38") (pinfunction "VSS_4_38") (pintype "unspecified"))
      (node (ref "U1") (pin "51") (pinfunction "VSS_6_51") (pintype "unspecified"))
      (node (ref "U1") (pin "61") (pinfunction "VSS_7_61") (pintype "unspecified"))
      (node (ref "U1") (pin "71") (pinfunction "VSS_1_71") (pintype "unspecified"))
      (node (ref "U1") (pin "83") (pinfunction "VSS_8_83") (pintype "unspecified"))
      (node (ref "U1") (pin "94") (pinfunction "VSS_9_94") (pintype "unspecified"))
      (node (ref "U10") (pin "12") (pinfunction "12_12") (pintype "unspecified"))
      (node (ref "U10") (pin "14") (pinfunction "14_14") (pintype "unspecified"))
      (node (ref "U11") (pin "12") (pinfunction "12_12") (pintype "unspecified"))
      (node (ref "U11") (pin "14") (pinfunction "14_14") (pintype "unspecified"))
      (node (ref "U12") (pin "12") (pinfunction "12_12") (pintype "unspecified"))
      (node (ref "U12") (pin "14") (pinfunction "14_14") (pintype "unspecified"))
      (node (ref "U13") (pin "12") (pinfunction "12_12") (pintype "unspecified"))
      (node (ref "U13") (pin "14") (pinfunction "14_14") (pintype "unspecified"))
      (node (ref "U14") (pin "12") (pinfunction "12_12") (pintype "unspecified"))
      (node (ref "U14") (pin "14") (pinfunction "14_14") (pintype "unspecified"))
      (node (ref "U2") (pin "1") (pinfunction "GND_1") (pintype "unspecified"))
      (node (ref "U3") (pin "2") (pinfunction "GND_2") (pintype "unspecified"))
      (node (ref "U4") (pin "4") (pinfunction "4_4") (pintype "unspecified"))
      (node (ref "U5") (pin "12") (pinfunction "12_12") (pintype "unspecified"))
      (node (ref "U5") (pin "14") (pinfunction "14_14") (pintype "unspecified"))
      (node (ref "U6") (pin "12") (pinfunction "12_12") (pintype "unspecified"))
      (node (ref "U6") (pin "14") (pinfunction "14_14") (pintype "unspecified"))
      (node (ref "U7") (pin "12") (pinfunction "12_12") (pintype "unspecified"))
      (node (ref "U7") (pin "14") (pinfunction "14_14") (pintype "unspecified"))
      (node (ref "U8") (pin "12") (pinfunction "12_12") (pintype "unspecified"))
      (node (ref "U8") (pin "14") (pinfunction "14_14") (pintype "unspecified"))
      (node (ref "U9") (pin "12") (pinfunction "12_12") (pintype "unspecified"))
      (node (ref "U9") (pin "14") (pinfunction "14_14") (pintype "unspecified"))
    )
    (net (code "5") (name "L1_IN") (class "Default")
      (node (ref "U1") (pin "82") (pinfunction "PD13_82") (pintype "unspecified"))
      (node (ref "U5") (pin "9") (pinfunction "9_9") (pintype "unspecified"))
    )
    (net (code "6") (name "L1_OUT") (class "Default")
      (node (ref "U5") (pin "10") (pinfunction "10_10") (pintype "unspecified"))
    )
    (net (code "7") (name "L2_IN") (class "Default")
      (node (ref "U1") (pin "36") (pinfunction "PA2_36") (pintype "unspecified"))
      (node (ref "U6") (pin "9") (pinfunction "9_9") (pintype "unspecified"))
    )
    (net (code "8") (name "L2_OUT") (class "Default")
      (node (ref "U6") (pin "10") (pinfunction "10_10") (pintype "unspecified"))
    )
    (net (code "9") (name "L3_IN") (class "Default")
      (node (ref "U1") (pin "35") (pinfunction "PA1_35") (pintype "unspecified"))
      (node (ref "U7") (pin "9") (pinfunction "9_9") (pintype "unspecified"))
    )
    (net (code "10") (name "L3_OUT") (class "Default")
      (node (ref "U7") (pin "10") (pinfunction "10_10") (pintype "unspecified"))
    )
    (net (code "11") (name "L4_IN") (class "Default")
      (node (ref "U1") (pin "42") (pinfunction "PA6_42") (pintype "unspecified"))
      (node (ref "U8") (pin "9") (pinfunction "9_9") (pintype "unspecified"))
    )
    (net (code "12") (name "L4_OUT") (class "Default")
      (node (ref "U8") (pin "10") (pinfunction "10_10") (pintype "unspecified"))
    )
    (net (code "13") (name "L5_IN") (class "Default")
      (node (ref "U1") (pin "46") (pinfunction "PB0_46") (pintype "unspecified"))
      (node (ref "U9") (pin "9") (pinfunction "9_9") (pintype "unspecified"))
    )
    (net (code "14") (name "L5_OUT") (class "Default")
      (node (ref "U9") (pin "10") (pinfunction "10_10") (pintype "unspecified"))
    )
    (net (code "15") (name "L6_IN") (class "Default")
      (node (ref "U1") (pin "47") (pinfunction "PB1_47") (pintype "unspecified"))
      (node (ref "U10") (pin "9") (pinfunction "9_9") (pintype "unspecified"))
    )
    (net (code "16") (name "L6_OUT") (class "Default")
      (node (ref "U10") (pin "10") (pinfunction "10_10") (pintype "unspecified"))
    )
    (net (code "17") (name "L7_IN") (class "Default")
      (node (ref "U1") (pin "85") (pinfunction "PD14_85") (pintype "unspecified"))
      (node (ref "U11") (pin "9") (pinfunction "9_9") (pintype "unspecified"))
    )
    (net (code "18") (name "L7_OUT") (class "Default")
      (node (ref "U11") (pin "10") (pinfunction "10_10") (pintype "unspecified"))
    )
    (net (code "19") (name "L8_IN") (class "Default")
      (node (ref "U1") (pin "37") (pinfunction "PA3_37") (pintype "unspecified"))
      (node (ref "U12") (pin "9") (pinfunction "9_9") (pintype "unspecified"))
    )
    (net (code "20") (name "L8_OUT") (class "Default")
      (node (ref "U12") (pin "10") (pinfunction "10_10") (pintype "unspecified"))
    )
    (net (code "21") (name "L9_IN") (class "Default")
      (node (ref "U1") (pin "99") (pinfunction "PC9_99") (pintype "unspecified"))
      (node (ref "U13") (pin "9") (pinfunction "9_9") (pintype "unspecified"))
    )
    (net (code "22") (name "L9_OUT") (class "Default")
      (node (ref "U13") (pin "10") (pinfunction "10_10") (pintype "unspecified"))
    )
    (net (code "23") (name "L10_IN") (class "Default")
      (node (ref "U1") (pin "96") (pinfunction "PC6_96") (pintype "unspecified"))
      (node (ref "U14") (pin "9") (pinfunction "9_9") (pintype "unspecified"))
    )
    (net (code "24") (name "L10_OUT") (class "Default")
      (node (ref "U14") (pin "10") (pinfunction "10_10") (pintype "unspecified"))
    )
    (net (code "25") (name "LED1") (class "Default")
      (node (ref "R18") (pin "1") (pinfunction "1_1") (pintype "input"))
      (node (ref "U1") (pin "7") (pinfunction "PC13-TAMPER-RTC_7") (pintype "unspecified"))
    )
    (net (code "26") (name "LED2") (class "Default")
      (node (ref "R19") (pin "1") (pinfunction "1_1") (pintype "input"))
      (node (ref "U1") (pin "10") (pinfunction "PF0_10") (pintype "unspecified"))
    )
    (net (code "27") (name "Net-(LED4-K)") (class "Default")
      (node (ref "LED4") (pin "1") (pinfunction "K_1") (pintype "unspecified"))
      (node (ref "R18") (pin "2") (pinfunction "2_2") (pintype "input"))
    )
    (net (code "28") (name "Net-(LED5-K)") (class "Default")
      (node (ref "LED5") (pin "1") (pinfunction "K_1") (pintype "unspecified"))
      (node (ref "R19") (pin "2") (pinfunction "2_2") (pintype "input"))
    )
    (net (code "29") (name "Net-(LED6-K)") (class "Default")
      (node (ref "LED6") (pin "1") (pinfunction "K_1") (pintype "unspecified"))
      (node (ref "R20") (pin "2") (pinfunction "2_2") (pintype "input"))
    )
    (net (code "30") (name "Net-(U3-CANH)") (class "Default")
      (node (ref "P1") (pin "2") (pinfunction "2_2") (pintype "input"))
      (node (ref "U3") (pin "7") (pinfunction "CANH_7") (pintype "unspecified"))
    )
    (net (code "31") (name "Net-(U3-CANL)") (class "Default")
      (node (ref "P1") (pin "1") (pinfunction "1_1") (pintype "input"))
      (node (ref "U3") (pin "6") (pinfunction "CANL_6") (pintype "unspecified"))
    )
    (net (code "32") (name "Net-(U3-RS)") (class "Default")
      (node (ref "R17") (pin "1") (pinfunction "1_1") (pintype "input"))
      (node (ref "U3") (pin "8") (pinfunction "RS_8") (pintype "unspecified"))
    )
    (net (code "33") (name "OSC_IN") (class "Default")
      (node (ref "C22") (pin "2") (pinfunction "2_2") (pintype "input"))
      (node (ref "U1") (pin "23") (pinfunction "OSC_IN_23") (pintype "unspecified"))
      (node (ref "X1") (pin "1") (pinfunction "OSC1_1") (pintype "input"))
    )
    (net (code "34") (name "OSC_OUT") (class "Default")
      (node (ref "C23") (pin "2") (pinfunction "2_2") (pintype "input"))
      (node (ref "U1") (pin "24") (pinfunction "OSC_OUT_24") (pintype "unspecified"))
      (node (ref "X1") (pin "2") (pinfunction "OSC2_2") (pintype "input"))
    )
    (net (code "35") (name "R1_1") (class "Default")
      (node (ref "R10") (pin "1") (pinfunction "1_1") (pintype "input"))
      (node (ref "U1") (pin "81") (pinfunction "PD12_81") (pintype "unspecified"))
      (node (ref "U5") (pin "7") (pinfunction "7_7") (pintype "unspecified"))
    )
    (net (code "36") (name "R1_2") (class "Default")
      (node (ref "R14") (pin "1") (pinfunction "1_1") (pintype "input"))
      (node (ref "U1") (pin "79") (pinfunction "PD10_79") (pintype "unspecified"))
      (node (ref "U5") (pin "8") (pinfunction "8_8") (pintype "unspecified"))
    )
    (net (code "37") (name "R2_1") (class "Default")
      (node (ref "R9") (pin "1") (pinfunction "1_1") (pintype "input"))
      (node (ref "U1") (pin "77") (pinfunction "PD8_77") (pintype "unspecified"))
      (node (ref "U5") (pin "5") (pinfunction "5_5") (pintype "unspecified"))
    )
    (net (code "38") (name "R2_2") (class "Default")
      (node (ref "R13") (pin "1") (pinfunction "1_1") (pintype "input"))
      (node (ref "U1") (pin "78") (pinfunction "PD9_78") (pintype "unspecified"))
      (node (ref "U5") (pin "6") (pinfunction "6_6") (pintype "unspecified"))
    )
    (net (code "39") (name "R3_1") (class "Default")
      (node (ref "R8") (pin "1") (pinfunction "1_1") (pintype "input"))
      (node (ref "U1") (pin "75") (pinfunction "PB14_75") (pintype "unspecified"))
      (node (ref "U5") (pin "3") (pinfunction "3_3") (pintype "unspecified"))
    )
    (net (code "40") (name "R3_2") (class "Default")
      (node (ref "R12") (pin "1") (pinfunction "1_1") (pintype "input"))
      (node (ref "U1") (pin "76") (pinfunction "PB15_76") (pintype "unspecified"))
      (node (ref "U5") (pin "4") (pinfunction "4_4") (pintype "unspecified"))
    )
    (net (code "41") (name "R4_1") (class "Default")
      (node (ref "R7") (pin "1") (pinfunction "1_1") (pintype "input"))
      (node (ref "U1") (pin "73") (pinfunction "PB12_73") (pintype "unspecified"))
      (node (ref "U5") (pin "1") (pinfunction "1_1") (pintype "unspecified"))
    )
    (net (code "42") (name "R4_2") (class "Default")
      (node (ref "R11") (pin "1") (pinfunction "1_1") (pintype "input"))
      (node (ref "U1") (pin "74") (pinfunction "PB13_74") (pintype "unspecified"))
      (node (ref "U5") (pin "2") (pinfunction "2_2") (pintype "unspecified"))
    )
    (net (code "43") (name "R5_1") (class "Default")
      (node (ref "R24") (pin "1") (pinfunction "1_1") (pintype "input"))
      (node (ref "U1") (pin "87") (pinfunction "PG2_87") (pintype "unspecified"))
      (node (ref "U6") (pin "7") (pinfunction "7_7") (pintype "unspecified"))
    )
    (net (code "44") (name "R5_2") (class "Default")
      (node (ref "R28") (pin "1") (pinfunction "1_1") (pintype "input"))
      (node (ref "U1") (pin "88") (pinfunction "PG3_88") (pintype "unspecified"))
      (node (ref "U6") (pin "8") (pinfunction "8_8") (pintype "unspecified"))
    )
    (net (code "45") (name "R6_1") (class "Default")
      (node (ref "R23") (pin "1") (pinfunction "1_1") (pintype "input"))
      (node (ref "U1") (pin "89") (pinfunction "PG4_89") (pintype "unspecified"))
      (node (ref "U6") (pin "5") (pinfunction "5_5") (pintype "unspecified"))
    )
    (net (code "46") (name "R6_2") (class "Default")
      (node (ref "R27") (pin "1") (pinfunction "1_1") (pintype "input"))
      (node (ref "U1") (pin "70") (pinfunction "PB11_70") (pintype "unspecified"))
      (node (ref "U6") (pin "6") (pinfunction "6_6") (pintype "unspecified"))
    )
    (net (code "47") (name "R7_1") (class "Default")
      (node (ref "R22") (pin "1") (pinfunction "1_1") (pintype "input"))
      (node (ref "U1") (pin "69") (pinfunction "PB10_69") (pintype "unspecified"))
      (node (ref "U6") (pin "3") (pinfunction "3_3") (pintype "unspecified"))
    )
    (net (code "48") (name "R7_2") (class "Default")
      (node (ref "R26") (pin "1") (pinfunction "1_1") (pintype "input"))
      (node (ref "U1") (pin "68") (pinfunction "PE15_68") (pintype "unspecified"))
      (node (ref "U6") (pin "4") (pinfunction "4_4") (pintype "unspecified"))
    )
    (net (code "49") (name "R8_1") (class "Default")
      (node (ref "R21") (pin "1") (pinfunction "1_1") (pintype "input"))
      (node (ref "U1") (pin "65") (pinfunction "PE12_65") (pintype "unspecified"))
      (node (ref "U6") (pin "1") (pinfunction "1_1") (pintype "unspecified"))
    )
    (net (code "50") (name "R8_2") (class "Default")
      (node (ref "R25") (pin "1") (pinfunction "1_1") (pintype "input"))
      (node (ref "U1") (pin "64") (pinfunction "PE11_64") (pintype "unspecified"))
      (node (ref "U6") (pin "2") (pinfunction "2_2") (pintype "unspecified"))
    )
    (net (code "51") (name "R9_1") (class "Default")
      (node (ref "R80") (pin "1") (pinfunction "1_1") (pintype "input"))
      (node (ref "U1") (pin "63") (pinfunction "PE10_63") (pintype "unspecified"))
      (node (ref "U7") (pin "7") (pinfunction "7_7") (pintype "unspecified"))
    )
    (net (code "52") (name "R9_2") (class "Default")
      (node (ref "R84") (pin "1") (pinfunction "1_1") (pintype "input"))
      (node (ref "U1") (pin "60") (pinfunction "PE9_60") (pintype "unspecified"))
      (node (ref "U7") (pin "8") (pinfunction "8_8") (pintype "unspecified"))
    )
    (net (code "53") (name "R10_1") (class "Default")
      (node (ref "R79") (pin "1") (pinfunction "1_1") (pintype "input"))
      (node (ref "U1") (pin "59") (pinfunction "PE8_59") (pintype "unspecified"))
      (node (ref "U7") (pin "5") (pinfunction "5_5") (pintype "unspecified"))
    )
    (net (code "54") (name "R10_2") (class "Default")
      (node (ref "R83") (pin "1") (pinfunction "1_1") (pintype "input"))
      (node (ref "U1") (pin "58") (pinfunction "PE7_58") (pintype "unspecified"))
      (node (ref "U7") (pin "6") (pinfunction "6_6") (pintype "unspecified"))
    )
    (net (code "55") (name "R11_1") (class "Default")
      (node (ref "R78") (pin "1") (pinfunction "1_1") (pintype "input"))
      (node (ref "U1") (pin "57") (pinfunction "PG1_57") (pintype "unspecified"))
      (node (ref "U7") (pin "3") (pinfunction "3_3") (pintype "unspecified"))
    )
    (net (code "56") (name "R11_2") (class "Default")
      (node (ref "R82") (pin "1") (pinfunction "1_1") (pintype "input"))
      (node (ref "U1") (pin "56") (pinfunction "PG0_56") (pintype "unspecified"))
      (node (ref "U7") (pin "4") (pinfunction "4_4") (pintype "unspecified"))
    )
    (net (code "57") (name "R12_1") (class "Default")
      (node (ref "R77") (pin "1") (pinfunction "1_1") (pintype "input"))
      (node (ref "U1") (pin "55") (pinfunction "PF15_55") (pintype "unspecified"))
      (node (ref "U7") (pin "1") (pinfunction "1_1") (pintype "unspecified"))
    )
    (net (code "58") (name "R12_2") (class "Default")
      (node (ref "R81") (pin "1") (pinfunction "1_1") (pintype "input"))
      (node (ref "U1") (pin "50") (pinfunction "PF12_50") (pintype "unspecified"))
      (node (ref "U7") (pin "2") (pinfunction "2_2") (pintype "unspecified"))
    )
    (net (code "59") (name "R13_1") (class "Default")
      (node (ref "R88") (pin "1") (pinfunction "1_1") (pintype "input"))
      (node (ref "U1") (pin "49") (pinfunction "PF11_49") (pintype "unspecified"))
      (node (ref "U8") (pin "7") (pinfunction "7_7") (pintype "unspecified"))
    )
    (net (code "60") (name "R13_2") (class "Default")
      (node (ref "R92") (pin "1") (pinfunction "1_1") (pintype "input"))
      (node (ref "U1") (pin "48") (pinfunction "PB2_48") (pintype "unspecified"))
      (node (ref "U8") (pin "8") (pinfunction "8_8") (pintype "unspecified"))
    )
    (net (code "61") (name "R14_1") (class "Default")
      (node (ref "R87") (pin "1") (pinfunction "1_1") (pintype "input"))
      (node (ref "U1") (pin "41") (pinfunction "PA5_41") (pintype "unspecified"))
      (node (ref "U8") (pin "5") (pinfunction "5_5") (pintype "unspecified"))
    )
    (net (code "62") (name "R14_2") (class "Default")
      (node (ref "R91") (pin "1") (pinfunction "1_1") (pintype "input"))
      (node (ref "U1") (pin "40") (pinfunction "PA4_40") (pintype "unspecified"))
      (node (ref "U8") (pin "6") (pinfunction "6_6") (pintype "unspecified"))
    )
    (net (code "63") (name "R15_1") (class "Default")
      (node (ref "R86") (pin "1") (pinfunction "1_1") (pintype "input"))
      (node (ref "U1") (pin "44") (pinfunction "PC4_44") (pintype "unspecified"))
      (node (ref "U8") (pin "3") (pinfunction "3_3") (pintype "unspecified"))
    )
    (net (code "64") (name "R15_2") (class "Default")
      (node (ref "R90") (pin "1") (pinfunction "1_1") (pintype "input"))
      (node (ref "U1") (pin "45") (pinfunction "PC5_45") (pintype "unspecified"))
      (node (ref "U8") (pin "4") (pinfunction "4_4") (pintype "unspecified"))
    )
    (net (code "65") (name "R16_1") (class "Default")
      (node (ref "R85") (pin "1") (pinfunction "1_1") (pintype "input"))
      (node (ref "U1") (pin "53") (pinfunction "PF13_53") (pintype "unspecified"))
      (node (ref "U8") (pin "1") (pinfunction "1_1") (pintype "unspecified"))
    )
    (net (code "66") (name "R16_2") (class "Default")
      (node (ref "R89") (pin "1") (pinfunction "1_1") (pintype "input"))
      (node (ref "U1") (pin "54") (pinfunction "PF14_54") (pintype "unspecified"))
      (node (ref "U8") (pin "2") (pinfunction "2_2") (pintype "unspecified"))
    )
    (net (code "67") (name "R17_1") (class "Default")
      (node (ref "R32") (pin "1") (pinfunction "1_1") (pintype "input"))
      (node (ref "U1") (pin "19") (pinfunction "PF7_19") (pintype "unspecified"))
      (node (ref "U9") (pin "7") (pinfunction "7_7") (pintype "unspecified"))
    )
    (net (code "68") (name "R17_2") (class "Default")
      (node (ref "R36") (pin "1") (pinfunction "1_1") (pintype "input"))
      (node (ref "U1") (pin "20") (pinfunction "PF8_20") (pintype "unspecified"))
      (node (ref "U9") (pin "8") (pinfunction "8_8") (pintype "unspecified"))
    )
    (net (code "69") (name "R18_1") (class "Default")
      (node (ref "R31") (pin "1") (pinfunction "1_1") (pintype "input"))
      (node (ref "U1") (pin "21") (pinfunction "PF9_21") (pintype "unspecified"))
      (node (ref "U9") (pin "5") (pinfunction "5_5") (pintype "unspecified"))
    )
    (net (code "70") (name "R18_2") (class "Default")
      (node (ref "R35") (pin "1") (pinfunction "1_1") (pintype "input"))
      (node (ref "U1") (pin "22") (pinfunction "PF10_22") (pintype "unspecified"))
      (node (ref "U9") (pin "6") (pinfunction "6_6") (pintype "unspecified"))
    )
    (net (code "71") (name "R19_1") (class "Default")
      (node (ref "R30") (pin "1") (pinfunction "1_1") (pintype "input"))
      (node (ref "U1") (pin "26") (pinfunction "PC0_26") (pintype "unspecified"))
      (node (ref "U9") (pin "3") (pinfunction "3_3") (pintype "unspecified"))
    )
    (net (code "72") (name "R19_2") (class "Default")
      (node (ref "R34") (pin "1") (pinfunction "1_1") (pintype "input"))
      (node (ref "U1") (pin "27") (pinfunction "PC1_27") (pintype "unspecified"))
      (node (ref "U9") (pin "4") (pinfunction "4_4") (pintype "unspecified"))
    )
    (net (code "73") (name "R20_1") (class "Default")
      (node (ref "R29") (pin "1") (pinfunction "1_1") (pintype "input"))
      (node (ref "U1") (pin "28") (pinfunction "PC2_28") (pintype "unspecified"))
      (node (ref "U9") (pin "1") (pinfunction "1_1") (pintype "unspecified"))
    )
    (net (code "74") (name "R20_2") (class "Default")
      (node (ref "R33") (pin "1") (pinfunction "1_1") (pintype "input"))
      (node (ref "U1") (pin "29") (pinfunction "PC3_29") (pintype "unspecified"))
      (node (ref "U9") (pin "2") (pinfunction "2_2") (pintype "unspecified"))
    )
    (net (code "75") (name "R21_1") (class "Default")
      (node (ref "R40") (pin "1") (pinfunction "1_1") (pintype "input"))
      (node (ref "U1") (pin "15") (pinfunction "PF5_15") (pintype "unspecified"))
      (node (ref "U10") (pin "7") (pinfunction "7_7") (pintype "unspecified"))
    )
    (net (code "76") (name "R21_2") (class "Default")
      (node (ref "R44") (pin "1") (pinfunction "1_1") (pintype "input"))
      (node (ref "U1") (pin "18") (pinfunction "PF6_18") (pintype "unspecified"))
      (node (ref "U10") (pin "8") (pinfunction "8_8") (pintype "unspecified"))
    )
    (net (code "77") (name "R22_1") (class "Default")
      (node (ref "R39") (pin "1") (pinfunction "1_1") (pintype "input"))
      (node (ref "U1") (pin "13") (pinfunction "PF3_13") (pintype "unspecified"))
      (node (ref "U10") (pin "5") (pinfunction "5_5") (pintype "unspecified"))
    )
    (net (code "78") (name "R22_2") (class "Default")
      (node (ref "R43") (pin "1") (pinfunction "1_1") (pintype "input"))
      (node (ref "U1") (pin "14") (pinfunction "PF4_14") (pintype "unspecified"))
      (node (ref "U10") (pin "6") (pinfunction "6_6") (pintype "unspecified"))
    )
    (net (code "79") (name "R23_1") (class "Default")
      (node (ref "R38") (pin "1") (pinfunction "1_1") (pintype "input"))
      (node (ref "U1") (pin "11") (pinfunction "PF1_11") (pintype "unspecified"))
      (node (ref "U10") (pin "3") (pinfunction "3_3") (pintype "unspecified"))
    )
    (net (code "80") (name "R23_2") (class "Default")
      (node (ref "R42") (pin "1") (pinfunction "1_1") (pintype "input"))
      (node (ref "U1") (pin "12") (pinfunction "PF2_12") (pintype "unspecified"))
      (node (ref "U10") (pin "4") (pinfunction "4_4") (pintype "unspecified"))
    )
    (net (code "81") (name "R24_1") (class "Default")
      (node (ref "R37") (pin "1") (pinfunction "1_1") (pintype "input"))
      (node (ref "U1") (pin "4") (pinfunction "PE5_4") (pintype "unspecified"))
      (node (ref "U10") (pin "1") (pinfunction "1_1") (pintype "unspecified"))
    )
    (net (code "82") (name "R24_2") (class "Default")
      (node (ref "R41") (pin "1") (pinfunction "1_1") (pintype "input"))
      (node (ref "U1") (pin "5") (pinfunction "PE6_5") (pintype "unspecified"))
      (node (ref "U10") (pin "2") (pinfunction "2_2") (pintype "unspecified"))
    )
    (net (code "83") (name "R25_1") (class "Default")
      (node (ref "R48") (pin "1") (pinfunction "1_1") (pintype "input"))
      (node (ref "U1") (pin "2") (pinfunction "PE3_2") (pintype "unspecified"))
      (node (ref "U11") (pin "7") (pinfunction "7_7") (pintype "unspecified"))
    )
    (net (code "84") (name "R25_2") (class "Default")
      (node (ref "R52") (pin "1") (pinfunction "1_1") (pintype "input"))
      (node (ref "U1") (pin "3") (pinfunction "PE4_3") (pintype "unspecified"))
      (node (ref "U11") (pin "8") (pinfunction "8_8") (pintype "unspecified"))
    )
    (net (code "85") (name "R26_1") (class "Default")
      (node (ref "R47") (pin "1") (pinfunction "1_1") (pintype "input"))
      (node (ref "U1") (pin "140") (pinfunction "PB9_140") (pintype "unspecified"))
      (node (ref "U11") (pin "5") (pinfunction "5_5") (pintype "unspecified"))
    )
    (net (code "86") (name "R26_2") (class "Default")
      (node (ref "R51") (pin "1") (pinfunction "1_1") (pintype "input"))
      (node (ref "U1") (pin "139") (pinfunction "PB8_139") (pintype "unspecified"))
      (node (ref "U11") (pin "6") (pinfunction "6_6") (pintype "unspecified"))
    )
    (net (code "87") (name "R27_1") (class "Default")
      (node (ref "R46") (pin "1") (pinfunction "1_1") (pintype "input"))
      (node (ref "U1") (pin "137") (pinfunction "PB7_137") (pintype "unspecified"))
      (node (ref "U11") (pin "3") (pinfunction "3_3") (pintype "unspecified"))
    )
    (net (code "88") (name "R27_2") (class "Default")
      (node (ref "R50") (pin "1") (pinfunction "1_1") (pintype "input"))
      (node (ref "U1") (pin "136") (pinfunction "PB6_136") (pintype "unspecified"))
      (node (ref "U11") (pin "4") (pinfunction "4_4") (pintype "unspecified"))
    )
    (net (code "89") (name "R28_1") (class "Default")
      (node (ref "R45") (pin "1") (pinfunction "1_1") (pintype "input"))
      (node (ref "U1") (pin "135") (pinfunction "PB5_135") (pintype "unspecified"))
      (node (ref "U11") (pin "1") (pinfunction "1_1") (pintype "unspecified"))
    )
    (net (code "90") (name "R28_2") (class "Default")
      (node (ref "R49") (pin "1") (pinfunction "1_1") (pintype "input"))
      (node (ref "U1") (pin "134") (pinfunction "PB4_134") (pintype "unspecified"))
      (node (ref "U11") (pin "2") (pinfunction "2_2") (pintype "unspecified"))
    )
    (net (code "91") (name "R29_1") (class "Default")
      (node (ref "R56") (pin "1") (pinfunction "1_1") (pintype "input"))
      (node (ref "U1") (pin "133") (pinfunction "PB3_133") (pintype "unspecified"))
      (node (ref "U12") (pin "7") (pinfunction "7_7") (pintype "unspecified"))
    )
    (net (code "92") (name "R29_2") (class "Default")
      (node (ref "R60") (pin "1") (pinfunction "1_1") (pintype "input"))
      (node (ref "U1") (pin "132") (pinfunction "PG15_132") (pintype "unspecified"))
      (node (ref "U12") (pin "8") (pinfunction "8_8") (pintype "unspecified"))
    )
    (net (code "93") (name "R30_1") (class "Default")
      (node (ref "R55") (pin "1") (pinfunction "1_1") (pintype "input"))
      (node (ref "U1") (pin "126") (pinfunction "PG11_126") (pintype "unspecified"))
      (node (ref "U12") (pin "5") (pinfunction "5_5") (pintype "unspecified"))
    )
    (net (code "94") (name "R30_2") (class "Default")
      (node (ref "R59") (pin "1") (pinfunction "1_1") (pintype "input"))
      (node (ref "U1") (pin "125") (pinfunction "PG10_125") (pintype "unspecified"))
      (node (ref "U12") (pin "6") (pinfunction "6_6") (pintype "unspecified"))
    )
    (net (code "95") (name "R31_1") (class "Default")
      (node (ref "R54") (pin "1") (pinfunction "1_1") (pintype "input"))
      (node (ref "U1") (pin "124") (pinfunction "PG9_124") (pintype "unspecified"))
      (node (ref "U12") (pin "3") (pinfunction "3_3") (pintype "unspecified"))
    )
    (net (code "96") (name "R31_2") (class "Default")
      (node (ref "R58") (pin "1") (pinfunction "1_1") (pintype "input"))
      (node (ref "U1") (pin "123") (pinfunction "PD7_123") (pintype "unspecified"))
      (node (ref "U12") (pin "4") (pinfunction "4_4") (pintype "unspecified"))
    )
    (net (code "97") (name "R32_1") (class "Default")
      (node (ref "R53") (pin "1") (pinfunction "1_1") (pintype "input"))
      (node (ref "U1") (pin "122") (pinfunction "PD6_122") (pintype "unspecified"))
      (node (ref "U12") (pin "1") (pinfunction "1_1") (pintype "unspecified"))
    )
    (net (code "98") (name "R32_2") (class "Default")
      (node (ref "R57") (pin "1") (pinfunction "1_1") (pintype "input"))
      (node (ref "U1") (pin "119") (pinfunction "PD5_119") (pintype "unspecified"))
      (node (ref "U12") (pin "2") (pinfunction "2_2") (pintype "unspecified"))
    )
    (net (code "99") (name "R33_1") (class "Default")
      (node (ref "R64") (pin "1") (pinfunction "1_1") (pintype "input"))
      (node (ref "U1") (pin "118") (pinfunction "PD4_118") (pintype "unspecified"))
      (node (ref "U13") (pin "7") (pinfunction "7_7") (pintype "unspecified"))
    )
    (net (code "100") (name "R33_2") (class "Default")
      (node (ref "R68") (pin "1") (pinfunction "1_1") (pintype "input"))
      (node (ref "U1") (pin "117") (pinfunction "PD3_117") (pintype "unspecified"))
      (node (ref "U13") (pin "8") (pinfunction "8_8") (pintype "unspecified"))
    )
    (net (code "101") (name "R34_1") (class "Default")
      (node (ref "R63") (pin "1") (pinfunction "1_1") (pintype "input"))
      (node (ref "U1") (pin "113") (pinfunction "PC12_113") (pintype "unspecified"))
      (node (ref "U13") (pin "5") (pinfunction "5_5") (pintype "unspecified"))
    )
    (net (code "102") (name "R34_2") (class "Default")
      (node (ref "R67") (pin "1") (pinfunction "1_1") (pintype "input"))
      (node (ref "U1") (pin "112") (pinfunction "PC11_112") (pintype "unspecified"))
      (node (ref "U13") (pin "6") (pinfunction "6_6") (pintype "unspecified"))
    )
    (net (code "103") (name "R35_1") (class "Default")
      (node (ref "R62") (pin "1") (pinfunction "1_1") (pintype "input"))
      (node (ref "U1") (pin "111") (pinfunction "PC10_111") (pintype "unspecified"))
      (node (ref "U13") (pin "3") (pinfunction "3_3") (pintype "unspecified"))
    )
    (net (code "104") (name "R35_2") (class "Default")
      (node (ref "R66") (pin "1") (pinfunction "1_1") (pintype "input"))
      (node (ref "U1") (pin "110") (pinfunction "PA15_110") (pintype "unspecified"))
      (node (ref "U13") (pin "4") (pinfunction "4_4") (pintype "unspecified"))
    )
    (net (code "105") (name "R36_1") (class "Default")
      (node (ref "R61") (pin "1") (pinfunction "1_1") (pintype "input"))
      (node (ref "U1") (pin "102") (pinfunction "PA10_102") (pintype "unspecified"))
      (node (ref "U13") (pin "1") (pinfunction "1_1") (pintype "unspecified"))
    )
    (net (code "106") (name "R36_2") (class "Default")
      (node (ref "R65") (pin "1") (pinfunction "1_1") (pintype "input"))
      (node (ref "U1") (pin "101") (pinfunction "PA9_101") (pintype "unspecified"))
      (node (ref "U13") (pin "2") (pinfunction "2_2") (pintype "unspecified"))
    )
    (net (code "107") (name "R37_1") (class "Default")
      (node (ref "R72") (pin "1") (pinfunction "1_1") (pintype "input"))
      (node (ref "U1") (pin "98") (pinfunction "PC8_98") (pintype "unspecified"))
      (node (ref "U14") (pin "7") (pinfunction "7_7") (pintype "unspecified"))
    )
    (net (code "108") (name "R37_2") (class "Default")
      (node (ref "R76") (pin "1") (pinfunction "1_1") (pintype "input"))
      (node (ref "U1") (pin "97") (pinfunction "PC7_97") (pintype "unspecified"))
      (node (ref "U14") (pin "8") (pinfunction "8_8") (pintype "unspecified"))
    )
    (net (code "109") (name "R38_1") (class "Default")
      (node (ref "R71") (pin "1") (pinfunction "1_1") (pintype "input"))
      (node (ref "U1") (pin "93") (pinfunction "PG8_93") (pintype "unspecified"))
      (node (ref "U14") (pin "5") (pinfunction "5_5") (pintype "unspecified"))
    )
    (net (code "110") (name "R38_2") (class "Default")
      (node (ref "R75") (pin "1") (pinfunction "1_1") (pintype "input"))
      (node (ref "U1") (pin "92") (pinfunction "PG7_92") (pintype "unspecified"))
      (node (ref "U14") (pin "6") (pinfunction "6_6") (pintype "unspecified"))
    )
    (net (code "111") (name "R39_1") (class "Default")
      (node (ref "R70") (pin "1") (pinfunction "1_1") (pintype "input"))
      (node (ref "U1") (pin "91") (pinfunction "PG6_91") (pintype "unspecified"))
      (node (ref "U14") (pin "3") (pinfunction "3_3") (pintype "unspecified"))
    )
    (net (code "112") (name "R39_2") (class "Default")
      (node (ref "R74") (pin "1") (pinfunction "1_1") (pintype "input"))
      (node (ref "U1") (pin "90") (pinfunction "PG5_90") (pintype "unspecified"))
      (node (ref "U14") (pin "4") (pinfunction "4_4") (pintype "unspecified"))
    )
    (net (code "113") (name "R40_1") (class "Default")
      (node (ref "R69") (pin "1") (pinfunction "1_1") (pintype "input"))
      (node (ref "U1") (pin "66") (pinfunction "PE13_66") (pintype "unspecified"))
      (node (ref "U14") (pin "1") (pinfunction "1_1") (pintype "unspecified"))
    )
    (net (code "114") (name "R40_2") (class "Default")
      (node (ref "R73") (pin "1") (pinfunction "1_1") (pintype "input"))
      (node (ref "U1") (pin "67") (pinfunction "PE14_67") (pintype "unspecified"))
      (node (ref "U14") (pin "2") (pinfunction "2_2") (pintype "unspecified"))
    )
    (net (code "115") (name "RESET") (class "Default")
      (node (ref "C24") (pin "2") (pinfunction "2_2") (pintype "unspecified"))
      (node (ref "R15") (pin "1") (pinfunction "1_1") (pintype "input"))
      (node (ref "SW1") (pin "3") (pinfunction "C_3") (pintype "unspecified"))
      (node (ref "SW1") (pin "4") (pinfunction "D_4") (pintype "unspecified"))
      (node (ref "U1") (pin "25") (pinfunction "NRST_25") (pintype "unspecified"))
    )
    (net (code "116") (name "SWCLK") (class "Default")
      (node (ref "U1") (pin "109") (pinfunction "PA14_109") (pintype "unspecified"))
      (node (ref "U4") (pin "3") (pinfunction "3_3") (pintype "unspecified"))
    )
    (net (code "117") (name "SWDIO") (class "Default")
      (node (ref "U1") (pin "105") (pinfunction "PA13_105") (pintype "unspecified"))
      (node (ref "U4") (pin "2") (pinfunction "2_2") (pintype "unspecified"))
    )
    (net (code "118") (name "VCC3V3") (class "Default")
      (node (ref "C20") (pin "2") (pinfunction "2_2") (pintype "input"))
      (node (ref "C21") (pin "2") (pinfunction "2_2") (pintype "input"))
      (node (ref "C26") (pin "2") (pinfunction "2_2") (pintype "unspecified"))
      (node (ref "C27") (pin "2") (pinfunction "2_2") (pintype "unspecified"))
      (node (ref "C28") (pin "2") (pinfunction "2_2") (pintype "unspecified"))
      (node (ref "C29") (pin "2") (pinfunction "2_2") (pintype "unspecified"))
      (node (ref "C30") (pin "2") (pinfunction "2_2") (pintype "unspecified"))
      (node (ref "C31") (pin "2") (pinfunction "2_2") (pintype "unspecified"))
      (node (ref "C32") (pin "2") (pinfunction "2_2") (pintype "unspecified"))
      (node (ref "C33") (pin "2") (pinfunction "2_2") (pintype "unspecified"))
      (node (ref "C34") (pin "2") (pinfunction "2_2") (pintype "unspecified"))
      (node (ref "C35") (pin "2") (pinfunction "2_2") (pintype "unspecified"))
      (node (ref "C36") (pin "2") (pinfunction "2_2") (pintype "unspecified"))
      (node (ref "C37") (pin "2") (pinfunction "2_2") (pintype "unspecified"))
      (node (ref "C38") (pin "2") (pinfunction "2_2") (pintype "unspecified"))
      (node (ref "LED4") (pin "2") (pinfunction "A_2") (pintype "unspecified"))
      (node (ref "LED5") (pin "2") (pinfunction "A_2") (pintype "unspecified"))
      (node (ref "LED6") (pin "2") (pinfunction "A_2") (pintype "unspecified"))
      (node (ref "R10") (pin "2") (pinfunction "2_2") (pintype "input"))
      (node (ref "R11") (pin "2") (pinfunction "2_2") (pintype "input"))
      (node (ref "R12") (pin "2") (pinfunction "2_2") (pintype "input"))
      (node (ref "R13") (pin "2") (pinfunction "2_2") (pintype "input"))
      (node (ref "R14") (pin "2") (pinfunction "2_2") (pintype "input"))
      (node (ref "R15") (pin "2") (pinfunction "2_2") (pintype "input"))
      (node (ref "R21") (pin "2") (pinfunction "2_2") (pintype "input"))
      (node (ref "R22") (pin "2") (pinfunction "2_2") (pintype "input"))
      (node (ref "R23") (pin "2") (pinfunction "2_2") (pintype "input"))
      (node (ref "R24") (pin "2") (pinfunction "2_2") (pintype "input"))
      (node (ref "R25") (pin "2") (pinfunction "2_2") (pintype "input"))
      (node (ref "R26") (pin "2") (pinfunction "2_2") (pintype "input"))
      (node (ref "R27") (pin "2") (pinfunction "2_2") (pintype "input"))
      (node (ref "R28") (pin "2") (pinfunction "2_2") (pintype "input"))
      (node (ref "R29") (pin "2") (pinfunction "2_2") (pintype "input"))
      (node (ref "R30") (pin "2") (pinfunction "2_2") (pintype "input"))
      (node (ref "R31") (pin "2") (pinfunction "2_2") (pintype "input"))
      (node (ref "R32") (pin "2") (pinfunction "2_2") (pintype "input"))
      (node (ref "R33") (pin "2") (pinfunction "2_2") (pintype "input"))
      (node (ref "R34") (pin "2") (pinfunction "2_2") (pintype "input"))
      (node (ref "R35") (pin "2") (pinfunction "2_2") (pintype "input"))
      (node (ref "R36") (pin "2") (pinfunction "2_2") (pintype "input"))
      (node (ref "R37") (pin "2") (pinfunction "2_2") (pintype "input"))
      (node (ref "R38") (pin "2") (pinfunction "2_2") (pintype "input"))
      (node (ref "R39") (pin "2") (pinfunction "2_2") (pintype "input"))
      (node (ref "R40") (pin "2") (pinfunction "2_2") (pintype "input"))
      (node (ref "R41") (pin "2") (pinfunction "2_2") (pintype "input"))
      (node (ref "R42") (pin "2") (pinfunction "2_2") (pintype "input"))
      (node (ref "R43") (pin "2") (pinfunction "2_2") (pintype "input"))
      (node (ref "R44") (pin "2") (pinfunction "2_2") (pintype "input"))
      (node (ref "R45") (pin "2") (pinfunction "2_2") (pintype "input"))
      (node (ref "R46") (pin "2") (pinfunction "2_2") (pintype "input"))
      (node (ref "R47") (pin "2") (pinfunction "2_2") (pintype "input"))
      (node (ref "R48") (pin "2") (pinfunction "2_2") (pintype "input"))
      (node (ref "R49") (pin "2") (pinfunction "2_2") (pintype "input"))
      (node (ref "R50") (pin "2") (pinfunction "2_2") (pintype "input"))
      (node (ref "R51") (pin "2") (pinfunction "2_2") (pintype "input"))
      (node (ref "R52") (pin "2") (pinfunction "2_2") (pintype "input"))
      (node (ref "R53") (pin "2") (pinfunction "2_2") (pintype "input"))
      (node (ref "R54") (pin "2") (pinfunction "2_2") (pintype "input"))
      (node (ref "R55") (pin "2") (pinfunction "2_2") (pintype "input"))
      (node (ref "R56") (pin "2") (pinfunction "2_2") (pintype "input"))
      (node (ref "R57") (pin "2") (pinfunction "2_2") (pintype "input"))
      (node (ref "R58") (pin "2") (pinfunction "2_2") (pintype "input"))
      (node (ref "R59") (pin "2") (pinfunction "2_2") (pintype "input"))
      (node (ref "R60") (pin "2") (pinfunction "2_2") (pintype "input"))
      (node (ref "R61") (pin "2") (pinfunction "2_2") (pintype "input"))
      (node (ref "R62") (pin "2") (pinfunction "2_2") (pintype "input"))
      (node (ref "R63") (pin "2") (pinfunction "2_2") (pintype "input"))
      (node (ref "R64") (pin "2") (pinfunction "2_2") (pintype "input"))
      (node (ref "R65") (pin "2") (pinfunction "2_2") (pintype "input"))
      (node (ref "R66") (pin "2") (pinfunction "2_2") (pintype "input"))
      (node (ref "R67") (pin "2") (pinfunction "2_2") (pintype "input"))
      (node (ref "R68") (pin "2") (pinfunction "2_2") (pintype "input"))
      (node (ref "R69") (pin "2") (pinfunction "2_2") (pintype "input"))
      (node (ref "R7") (pin "2") (pinfunction "2_2") (pintype "input"))
      (node (ref "R70") (pin "2") (pinfunction "2_2") (pintype "input"))
      (node (ref "R71") (pin "2") (pinfunction "2_2") (pintype "input"))
      (node (ref "R72") (pin "2") (pinfunction "2_2") (pintype "input"))
      (node (ref "R73") (pin "2") (pinfunction "2_2") (pintype "input"))
      (node (ref "R74") (pin "2") (pinfunction "2_2") (pintype "input"))
      (node (ref "R75") (pin "2") (pinfunction "2_2") (pintype "input"))
      (node (ref "R76") (pin "2") (pinfunction "2_2") (pintype "input"))
      (node (ref "R77") (pin "2") (pinfunction "2_2") (pintype "input"))
      (node (ref "R78") (pin "2") (pinfunction "2_2") (pintype "input"))
      (node (ref "R79") (pin "2") (pinfunction "2_2") (pintype "input"))
      (node (ref "R8") (pin "2") (pinfunction "2_2") (pintype "input"))
      (node (ref "R80") (pin "2") (pinfunction "2_2") (pintype "input"))
      (node (ref "R81") (pin "2") (pinfunction "2_2") (pintype "input"))
      (node (ref "R82") (pin "2") (pinfunction "2_2") (pintype "input"))
      (node (ref "R83") (pin "2") (pinfunction "2_2") (pintype "input"))
      (node (ref "R84") (pin "2") (pinfunction "2_2") (pintype "input"))
      (node (ref "R85") (pin "2") (pinfunction "2_2") (pintype "input"))
      (node (ref "R86") (pin "2") (pinfunction "2_2") (pintype "input"))
      (node (ref "R87") (pin "2") (pinfunction "2_2") (pintype "input"))
      (node (ref "R88") (pin "2") (pinfunction "2_2") (pintype "input"))
      (node (ref "R89") (pin "2") (pinfunction "2_2") (pintype "input"))
      (node (ref "R9") (pin "2") (pinfunction "2_2") (pintype "input"))
      (node (ref "R90") (pin "2") (pinfunction "2_2") (pintype "input"))
      (node (ref "R91") (pin "2") (pinfunction "2_2") (pintype "input"))
      (node (ref "R92") (pin "2") (pinfunction "2_2") (pintype "input"))
      (node (ref "U1") (pin "108") (pinfunction "VDD_2_108") (pintype "unspecified"))
      (node (ref "U1") (pin "121") (pinfunction "VDD_10_121") (pintype "unspecified"))
      (node (ref "U1") (pin "131") (pinfunction "VDD_11_131") (pintype "unspecified"))
      (node (ref "U1") (pin "144") (pinfunction "VDD_3_144") (pintype "unspecified"))
      (node (ref "U1") (pin "17") (pinfunction "VDD_5_17") (pintype "unspecified"))
      (node (ref "U1") (pin "33") (pinfunction "VDDA_33") (pintype "unspecified"))
      (node (ref "U1") (pin "39") (pinfunction "VDD_4_39") (pintype "unspecified"))
      (node (ref "U1") (pin "52") (pinfunction "VDD_6_52") (pintype "unspecified"))
      (node (ref "U1") (pin "62") (pinfunction "VDD_7_62") (pintype "unspecified"))
      (node (ref "U1") (pin "72") (pinfunction "VDD_1_72") (pintype "unspecified"))
      (node (ref "U1") (pin "84") (pinfunction "VDD_8_84") (pintype "unspecified"))
      (node (ref "U1") (pin "95") (pinfunction "VDD_9_95") (pintype "unspecified"))
      (node (ref "U2") (pin "2") (pinfunction "VOUT_2") (pintype "unspecified"))
      (node (ref "U2") (pin "4") (pinfunction "VOUT_4") (pintype "unspecified"))
      (node (ref "U3") (pin "3") (pinfunction "VCC_3") (pintype "unspecified"))
    )
    (net (code "119") (name "VCC5V") (class "Default")
      (node (ref "C19") (pin "1") (pinfunction "1_1") (pintype "input"))
      (node (ref "C25") (pin "2") (pinfunction "2_2") (pintype "unspecified"))
      (node (ref "P2") (pin "2") (pinfunction "2_2") (pintype "input"))
      (node (ref "U10") (pin "11") (pinfunction "11_11") (pintype "unspecified"))
      (node (ref "U10") (pin "13") (pinfunction "13_13") (pintype "unspecified"))
      (node (ref "U11") (pin "11") (pinfunction "11_11") (pintype "unspecified"))
      (node (ref "U11") (pin "13") (pinfunction "13_13") (pintype "unspecified"))
      (node (ref "U12") (pin "11") (pinfunction "11_11") (pintype "unspecified"))
      (node (ref "U12") (pin "13") (pinfunction "13_13") (pintype "unspecified"))
      (node (ref "U13") (pin "11") (pinfunction "11_11") (pintype "unspecified"))
      (node (ref "U13") (pin "13") (pinfunction "13_13") (pintype "unspecified"))
      (node (ref "U14") (pin "11") (pinfunction "11_11") (pintype "unspecified"))
      (node (ref "U14") (pin "13") (pinfunction "13_13") (pintype "unspecified"))
      (node (ref "U2") (pin "3") (pinfunction "VIN_3") (pintype "unspecified"))
      (node (ref "U4") (pin "1") (pinfunction "1_1") (pintype "unspecified"))
      (node (ref "U5") (pin "11") (pinfunction "11_11") (pintype "unspecified"))
      (node (ref "U5") (pin "13") (pinfunction "13_13") (pintype "unspecified"))
      (node (ref "U6") (pin "11") (pinfunction "11_11") (pintype "unspecified"))
      (node (ref "U6") (pin "13") (pinfunction "13_13") (pintype "unspecified"))
      (node (ref "U7") (pin "11") (pinfunction "11_11") (pintype "unspecified"))
      (node (ref "U7") (pin "13") (pinfunction "13_13") (pintype "unspecified"))
      (node (ref "U8") (pin "11") (pinfunction "11_11") (pintype "unspecified"))
      (node (ref "U8") (pin "13") (pinfunction "13_13") (pintype "unspecified"))
      (node (ref "U9") (pin "11") (pinfunction "11_11") (pintype "unspecified"))
      (node (ref "U9") (pin "13") (pinfunction "13_13") (pintype "unspecified"))
    )
    (net (code "120") (name "unconnected-(U1-NC-Pad106)") (class "Default")
      (node (ref "U1") (pin "106") (pinfunction "NC_106") (pintype "unspecified"))
    )
    (net (code "121") (name "unconnected-(U1-PA0-WKUP-Pad34)") (class "Default")
      (node (ref "U1") (pin "34") (pinfunction "PA0-WKUP_34") (pintype "unspecified"))
    )
    (net (code "122") (name "unconnected-(U1-PA7-Pad43)") (class "Default")
      (node (ref "U1") (pin "43") (pinfunction "PA7_43") (pintype "unspecified"))
    )
    (net (code "123") (name "unconnected-(U1-PA8-Pad100)") (class "Default")
      (node (ref "U1") (pin "100") (pinfunction "PA8_100") (pintype "unspecified"))
    )
    (net (code "124") (name "unconnected-(U1-PA11-Pad103)") (class "Default")
      (node (ref "U1") (pin "103") (pinfunction "PA11_103") (pintype "unspecified"))
    )
    (net (code "125") (name "unconnected-(U1-PA12-Pad104)") (class "Default")
      (node (ref "U1") (pin "104") (pinfunction "PA12_104") (pintype "unspecified"))
    )
    (net (code "126") (name "unconnected-(U1-PC14-OSC32_IN-Pad8)") (class "Default")
      (node (ref "U1") (pin "8") (pinfunction "PC14-OSC32_IN_8") (pintype "unspecified"))
    )
    (net (code "127") (name "unconnected-(U1-PC15-OSC32_OUT-Pad9)") (class "Default")
      (node (ref "U1") (pin "9") (pinfunction "PC15-OSC32_OUT_9") (pintype "unspecified"))
    )
    (net (code "128") (name "unconnected-(U1-PD2-Pad116)") (class "Default")
      (node (ref "U1") (pin "116") (pinfunction "PD2_116") (pintype "unspecified"))
    )
    (net (code "129") (name "unconnected-(U1-PD11-Pad80)") (class "Default")
      (node (ref "U1") (pin "80") (pinfunction "PD11_80") (pintype "unspecified"))
    )
    (net (code "130") (name "unconnected-(U1-PD15-Pad86)") (class "Default")
      (node (ref "U1") (pin "86") (pinfunction "PD15_86") (pintype "unspecified"))
    )
    (net (code "131") (name "unconnected-(U1-PE0-Pad141)") (class "Default")
      (node (ref "U1") (pin "141") (pinfunction "PE0_141") (pintype "unspecified"))
    )
    (net (code "132") (name "unconnected-(U1-PE1-Pad142)") (class "Default")
      (node (ref "U1") (pin "142") (pinfunction "PE1_142") (pintype "unspecified"))
    )
    (net (code "133") (name "unconnected-(U1-PE2-Pad1)") (class "Default")
      (node (ref "U1") (pin "1") (pinfunction "PE2_1") (pintype "unspecified"))
    )
    (net (code "134") (name "unconnected-(U1-PG12-Pad127)") (class "Default")
      (node (ref "U1") (pin "127") (pinfunction "PG12_127") (pintype "unspecified"))
    )
    (net (code "135") (name "unconnected-(U1-PG13-Pad128)") (class "Default")
      (node (ref "U1") (pin "128") (pinfunction "PG13_128") (pintype "unspecified"))
    )
    (net (code "136") (name "unconnected-(U1-PG14-Pad129)") (class "Default")
      (node (ref "U1") (pin "129") (pinfunction "PG14_129") (pintype "unspecified"))
    )
    (net (code "137") (name "unconnected-(U1-VBAT-Pad6)") (class "Default")
      (node (ref "U1") (pin "6") (pinfunction "VBAT_6") (pintype "unspecified"))
    )
    (net (code "138") (name "unconnected-(U1-VREF+-Pad32)") (class "Default")
      (node (ref "U1") (pin "32") (pinfunction "VREF+_32") (pintype "unspecified"))
    )
    (net (code "139") (name "unconnected-(U1-VREF--Pad31)") (class "Default")
      (node (ref "U1") (pin "31") (pinfunction "VREF-_31") (pintype "unspecified"))
    )
    (net (code "140") (name "unconnected-(U1-VSS_5-Pad16)") (class "Default")
      (node (ref "U1") (pin "16") (pinfunction "VSS_5_16") (pintype "unspecified"))
    )
    (net (code "141") (name "unconnected-(U3-VREF-Pad5)") (class "Default")
      (node (ref "U3") (pin "5") (pinfunction "VREF_5") (pintype "unspecified"))
    )
  )
)
